# 28Pins_Schematic.net
KiCad netlist of a schematic drawn in Altium Designer
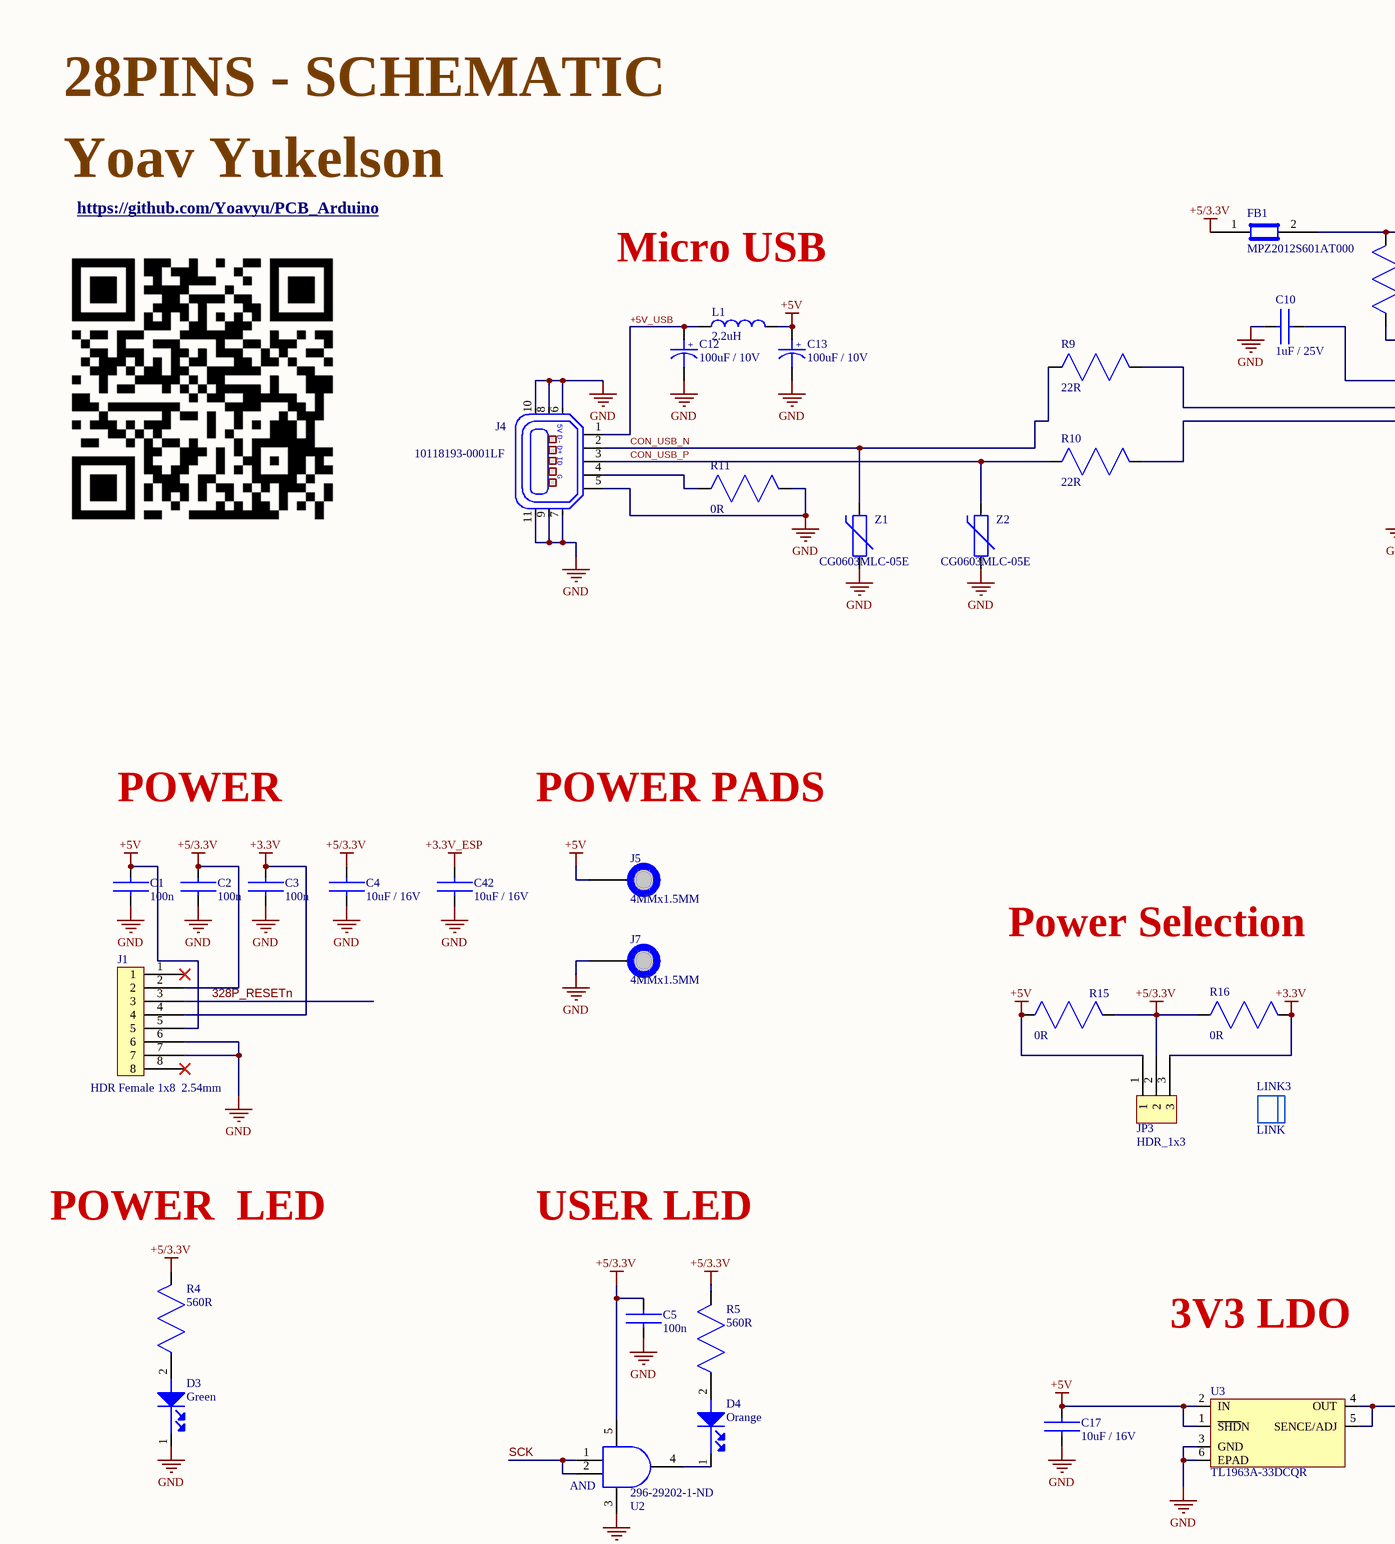
[diagram p0: 28Pins_Schematic.SchDoc, top left]
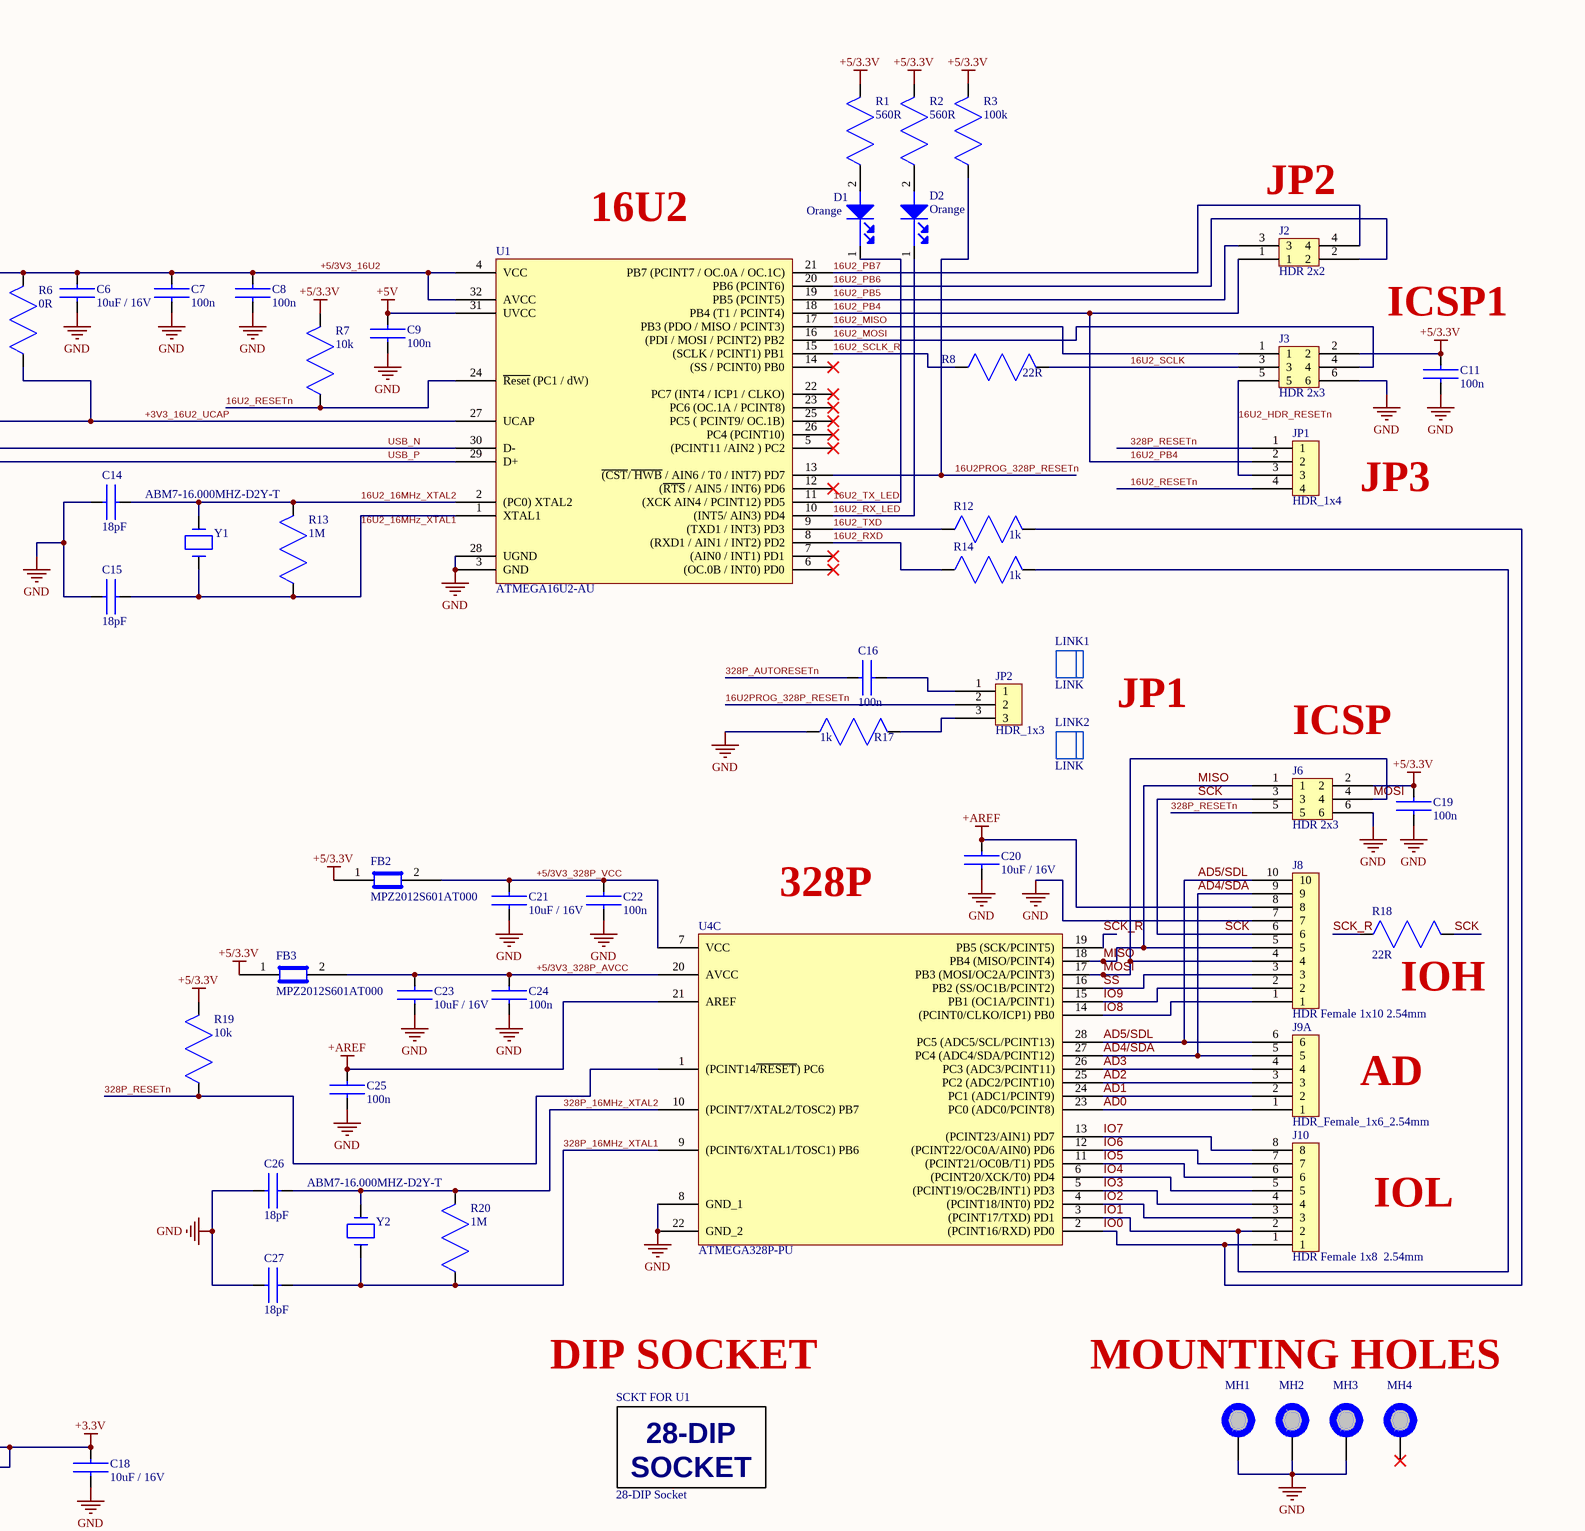
[diagram p1: 28Pins_Schematic.SchDoc, top right]
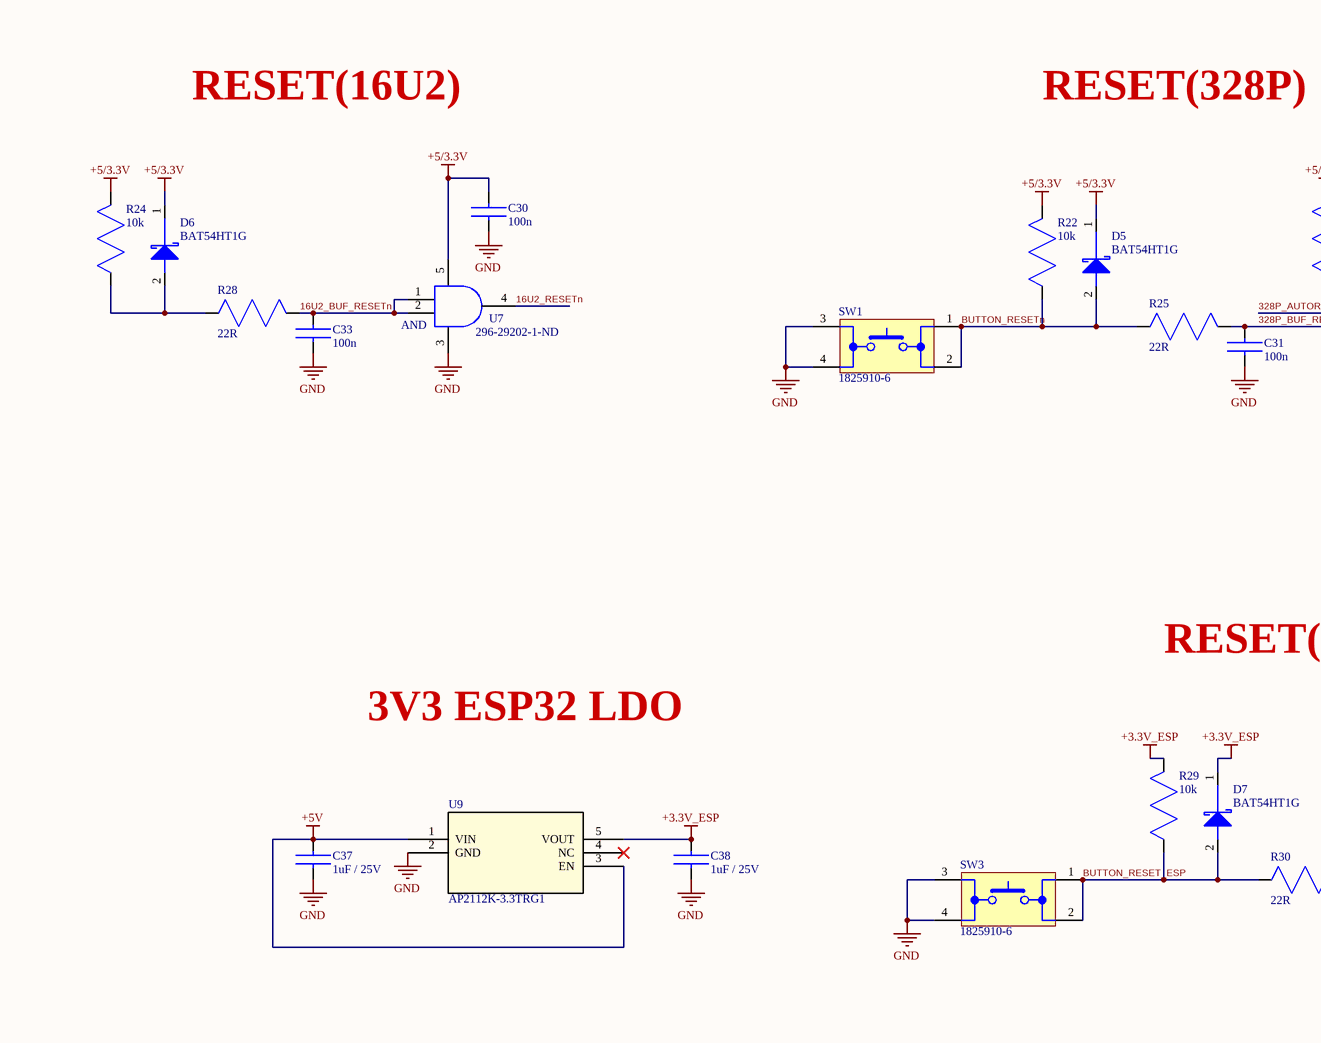
[diagram p2: 28Pins_Schematic.SchDoc, bottom left]
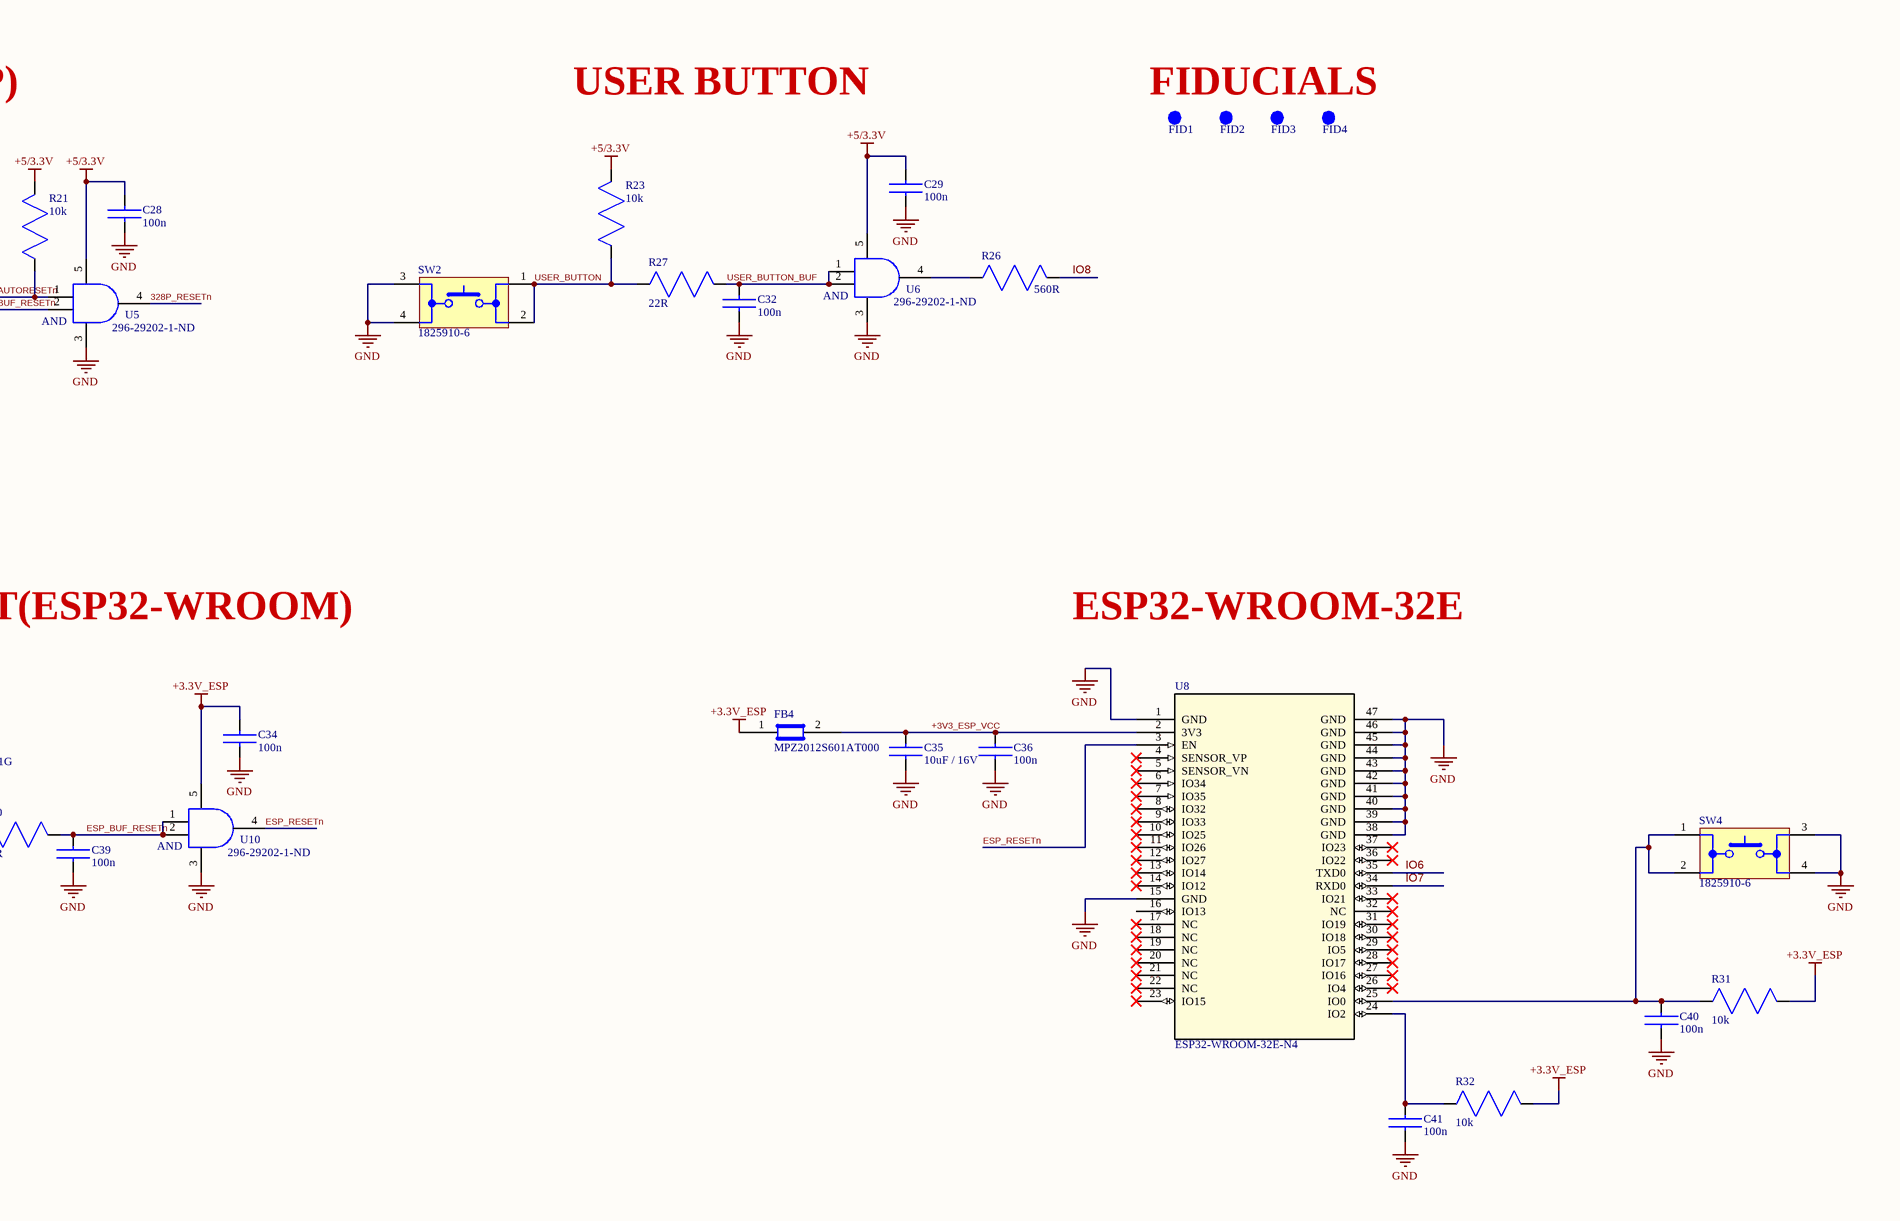
[diagram p3: 28Pins_Schematic.SchDoc, bottom right]

(export (version "E")
  (design (tool "Eeschema 10.0.6"))
  (components
    (comp (ref "C1")
      (value "100n")
      (footprint "C0805")
      (description "C Series 0805 0.1 uF 50 V ±10 % Tolerance X7R SMT Multilayer Ceramic Capacitor")
      (fields
        (field (name "MANUFACTURER") "TDK")
        (field (name "MANUFACTURER PART NUMBER") "C2012X7R1H104K085AA")
      )
      (libsource (lib "28Pins_Project_V1I1") (part "C2012X7R1H104K085AA"))
    )
    (comp (ref "C2")
      (value "100n")
      (footprint "C0805")
      (description "C Series 0805 0.1 uF 50 V ±10 % Tolerance X7R SMT Multilayer Ceramic Capacitor")
      (fields
        (field (name "MANUFACTURER") "TDK")
        (field (name "MANUFACTURER PART NUMBER") "C2012X7R1H104K085AA")
      )
      (libsource (lib "28Pins_Project_V1I1") (part "C2012X7R1H104K085AA"))
    )
    (comp (ref "C3")
      (value "100n")
      (footprint "C0805")
      (description "C Series 0805 0.1 uF 50 V ±10 % Tolerance X7R SMT Multilayer Ceramic Capacitor")
      (fields
        (field (name "MANUFACTURER") "TDK")
        (field (name "MANUFACTURER PART NUMBER") "C2012X7R1H104K085AA")
      )
      (libsource (lib "28Pins_Project_V1I1") (part "C2012X7R1H104K085AA"))
    )
    (comp (ref "C4")
      (value "10uF / 16V")
      (footprint "C0805")
      (description "C Series 0805 10 uF 16 V ±10 % Tolerance X5R SMT Multilayer Ceramic Capacitor")
      (fields
        (field (name "MANUFACTURER") "TDK")
        (field (name "MANUFACTURER PART NUMBER") "C2012X5R1C106K085AC")
      )
      (libsource (lib "28Pins_Project_V1I1") (part "C2012X5R1C106K085AC"))
    )
    (comp (ref "C5")
      (value "100n")
      (footprint "C0805")
      (description "C Series 0805 0.1 uF 50 V ±10 % Tolerance X7R SMT Multilayer Ceramic Capacitor")
      (fields
        (field (name "MANUFACTURER") "TDK")
        (field (name "MANUFACTURER PART NUMBER") "C2012X7R1H104K085AA")
      )
      (libsource (lib "28Pins_Project_V1I1") (part "C2012X7R1H104K085AA"))
    )
    (comp (ref "C6")
      (value "10uF / 16V")
      (footprint "C0805")
      (description "C Series 0805 10 uF 16 V ±10 % Tolerance X5R SMT Multilayer Ceramic Capacitor")
      (fields
        (field (name "MANUFACTURER") "TDK")
        (field (name "MANUFACTURER PART NUMBER") "C2012X5R1C106K085AC")
      )
      (libsource (lib "28Pins_Project_V1I1") (part "C2012X5R1C106K085AC"))
    )
    (comp (ref "C7")
      (value "100n")
      (footprint "C0805")
      (description "C Series 0805 0.1 uF 50 V ±10 % Tolerance X7R SMT Multilayer Ceramic Capacitor")
      (fields
        (field (name "MANUFACTURER") "TDK")
        (field (name "MANUFACTURER PART NUMBER") "C2012X7R1H104K085AA")
      )
      (libsource (lib "28Pins_Project_V1I1") (part "C2012X7R1H104K085AA"))
    )
    (comp (ref "C8")
      (value "100n")
      (footprint "C0805")
      (description "C Series 0805 0.1 uF 50 V ±10 % Tolerance X7R SMT Multilayer Ceramic Capacitor")
      (fields
        (field (name "MANUFACTURER") "TDK")
        (field (name "MANUFACTURER PART NUMBER") "C2012X7R1H104K085AA")
      )
      (libsource (lib "28Pins_Project_V1I1") (part "C2012X7R1H104K085AA"))
    )
    (comp (ref "C9")
      (value "100n")
      (footprint "C0805")
      (description "C Series 0805 0.1 uF 50 V ±10 % Tolerance X7R SMT Multilayer Ceramic Capacitor")
      (fields
        (field (name "MANUFACTURER") "TDK")
        (field (name "MANUFACTURER PART NUMBER") "C2012X7R1H104K085AA")
      )
      (libsource (lib "28Pins_Project_V1I1") (part "C2012X7R1H104K085AA"))
    )
    (comp (ref "C10")
      (value "1uF / 25V")
      (footprint "C0805")
      (description "C Series 0805 1 uF 25 V ±10% Tolerance X5R SMT Multilayer Ceramic Capacitor")
      (fields
        (field (name "MANUFACTURER") "TDK")
        (field (name "MANUFACTURER PART NUMBER") "C2012X5R1E105K125AA")
      )
      (libsource (lib "28Pins_Project_V1I1") (part "C2012X5R1E105K125AA"))
    )
    (comp (ref "C11")
      (value "100n")
      (footprint "C0805")
      (description "C Series 0805 0.1 uF 50 V ±10 % Tolerance X7R SMT Multilayer Ceramic Capacitor")
      (fields
        (field (name "MANUFACTURER") "TDK")
        (field (name "MANUFACTURER PART NUMBER") "C2012X7R1H104K085AA")
      )
      (libsource (lib "28Pins_Project_V1I1") (part "C2012X7R1H104K085AA"))
    )
    (comp (ref "C12")
      (value "100uF / 10V")
      (footprint "C_ALU_C_SIZE")
      (description "Radial Can - SMD ALUMINUM ELECTROLYTIC CAPACITOR S 10V 100muF ±20% 0.197Dia 5.00mm")
      (fields
        (field (name "MANUFACTURER") "Panasonic")
        (field (name "MANUFACTURER PART NUMBER") "EEE-1AA101WR")
      )
      (libsource (lib "28Pins_Project_V1I1") (part "EEE-1AA101WR"))
    )
    (comp (ref "C13")
      (value "100uF / 10V")
      (footprint "C_ALU_C_SIZE")
      (description "Radial Can - SMD ALUMINUM ELECTROLYTIC CAPACITOR S 10V 100muF ±20% 0.197Dia 5.00mm")
      (fields
        (field (name "MANUFACTURER") "Panasonic")
        (field (name "MANUFACTURER PART NUMBER") "EEE-1AA101WR")
      )
      (libsource (lib "28Pins_Project_V1I1") (part "EEE-1AA101WR"))
    )
    (comp (ref "C14")
      (value "18pF")
      (footprint "C0805")
      (description "SMD Comm C0G 0805 (2012Metric) Ceramic Capacitor 0.079Lx0.049W 2.00mmx1.25mm C0G NP0 ±5% 18pF")
      (fields
        (field (name "MANUFACTURER") "KEMET")
        (field (name "MANUFACTURER PART NUMBER") "C0805C180J5GACTU")
      )
      (libsource (lib "28Pins_Project_V1I1") (part "C0805C180J5GACTU"))
    )
    (comp (ref "C15")
      (value "18pF")
      (footprint "C0805")
      (description "SMD Comm C0G 0805 (2012Metric) Ceramic Capacitor 0.079Lx0.049W 2.00mmx1.25mm C0G NP0 ±5% 18pF")
      (fields
        (field (name "MANUFACTURER") "KEMET")
        (field (name "MANUFACTURER PART NUMBER") "C0805C180J5GACTU")
      )
      (libsource (lib "28Pins_Project_V1I1") (part "C0805C180J5GACTU"))
    )
    (comp (ref "C16")
      (value "100n")
      (footprint "C0805")
      (description "C Series 0805 0.1 uF 50 V ±10 % Tolerance X7R SMT Multilayer Ceramic Capacitor")
      (fields
        (field (name "MANUFACTURER") "TDK")
        (field (name "MANUFACTURER PART NUMBER") "C2012X7R1H104K085AA")
      )
      (libsource (lib "28Pins_Project_V1I1") (part "C2012X7R1H104K085AA"))
    )
    (comp (ref "C17")
      (value "10uF / 16V")
      (footprint "C0805")
      (description "C Series 0805 10 uF 16 V ±10 % Tolerance X5R SMT Multilayer Ceramic Capacitor")
      (fields
        (field (name "MANUFACTURER") "TDK")
        (field (name "MANUFACTURER PART NUMBER") "C2012X5R1C106K085AC")
      )
      (libsource (lib "28Pins_Project_V1I1") (part "C2012X5R1C106K085AC"))
    )
    (comp (ref "C18")
      (value "10uF / 16V")
      (footprint "C0805")
      (description "C Series 0805 10 uF 16 V ±10 % Tolerance X5R SMT Multilayer Ceramic Capacitor")
      (fields
        (field (name "MANUFACTURER") "TDK")
        (field (name "MANUFACTURER PART NUMBER") "C2012X5R1C106K085AC")
      )
      (libsource (lib "28Pins_Project_V1I1") (part "C2012X5R1C106K085AC"))
    )
    (comp (ref "C19")
      (value "100n")
      (footprint "C0805")
      (description "C Series 0805 0.1 uF 50 V ±10 % Tolerance X7R SMT Multilayer Ceramic Capacitor")
      (fields
        (field (name "MANUFACTURER") "TDK")
        (field (name "MANUFACTURER PART NUMBER") "C2012X7R1H104K085AA")
      )
      (libsource (lib "28Pins_Project_V1I1") (part "C2012X7R1H104K085AA"))
    )
    (comp (ref "C20")
      (value "10uF / 16V")
      (footprint "C0805")
      (description "C Series 0805 10 uF 16 V ±10 % Tolerance X5R SMT Multilayer Ceramic Capacitor")
      (fields
        (field (name "MANUFACTURER") "TDK")
        (field (name "MANUFACTURER PART NUMBER") "C2012X5R1C106K085AC")
      )
      (libsource (lib "28Pins_Project_V1I1") (part "C2012X5R1C106K085AC"))
    )
    (comp (ref "C21")
      (value "10uF / 16V")
      (footprint "C0805")
      (description "C Series 0805 10 uF 16 V ±10 % Tolerance X5R SMT Multilayer Ceramic Capacitor")
      (fields
        (field (name "MANUFACTURER") "TDK")
        (field (name "MANUFACTURER PART NUMBER") "C2012X5R1C106K085AC")
      )
      (libsource (lib "28Pins_Project_V1I1") (part "C2012X5R1C106K085AC"))
    )
    (comp (ref "C22")
      (value "100n")
      (footprint "C0805")
      (description "C Series 0805 0.1 uF 50 V ±10 % Tolerance X7R SMT Multilayer Ceramic Capacitor")
      (fields
        (field (name "MANUFACTURER") "TDK")
        (field (name "MANUFACTURER PART NUMBER") "C2012X7R1H104K085AA")
      )
      (libsource (lib "28Pins_Project_V1I1") (part "C2012X7R1H104K085AA"))
    )
    (comp (ref "C23")
      (value "10uF / 16V")
      (footprint "C0805")
      (description "C Series 0805 10 uF 16 V ±10 % Tolerance X5R SMT Multilayer Ceramic Capacitor")
      (fields
        (field (name "MANUFACTURER") "TDK")
        (field (name "MANUFACTURER PART NUMBER") "C2012X5R1C106K085AC")
      )
      (libsource (lib "28Pins_Project_V1I1") (part "C2012X5R1C106K085AC"))
    )
    (comp (ref "C24")
      (value "100n")
      (footprint "C0805")
      (description "C Series 0805 0.1 uF 50 V ±10 % Tolerance X7R SMT Multilayer Ceramic Capacitor")
      (fields
        (field (name "MANUFACTURER") "TDK")
        (field (name "MANUFACTURER PART NUMBER") "C2012X7R1H104K085AA")
      )
      (libsource (lib "28Pins_Project_V1I1") (part "C2012X7R1H104K085AA"))
    )
    (comp (ref "C25")
      (value "100n")
      (footprint "C0805")
      (description "C Series 0805 0.1 uF 50 V ±10 % Tolerance X7R SMT Multilayer Ceramic Capacitor")
      (fields
        (field (name "MANUFACTURER") "TDK")
        (field (name "MANUFACTURER PART NUMBER") "C2012X7R1H104K085AA")
      )
      (libsource (lib "28Pins_Project_V1I1") (part "C2012X7R1H104K085AA"))
    )
    (comp (ref "C26")
      (value "18pF")
      (footprint "C0805")
      (description "SMD Comm C0G 0805 (2012Metric) Ceramic Capacitor 0.079Lx0.049W 2.00mmx1.25mm C0G NP0 ±5% 18pF")
      (fields
        (field (name "MANUFACTURER") "KEMET")
        (field (name "MANUFACTURER PART NUMBER") "C0805C180J5GACTU")
      )
      (libsource (lib "28Pins_Project_V1I1") (part "C0805C180J5GACTU"))
    )
    (comp (ref "C27")
      (value "18pF")
      (footprint "C0805")
      (description "SMD Comm C0G 0805 (2012Metric) Ceramic Capacitor 0.079Lx0.049W 2.00mmx1.25mm C0G NP0 ±5% 18pF")
      (fields
        (field (name "MANUFACTURER") "KEMET")
        (field (name "MANUFACTURER PART NUMBER") "C0805C180J5GACTU")
      )
      (libsource (lib "28Pins_Project_V1I1") (part "C0805C180J5GACTU"))
    )
    (comp (ref "C28")
      (value "100n")
      (footprint "C0805")
      (description "C Series 0805 0.1 uF 50 V ±10 % Tolerance X7R SMT Multilayer Ceramic Capacitor")
      (fields
        (field (name "MANUFACTURER") "TDK")
        (field (name "MANUFACTURER PART NUMBER") "C2012X7R1H104K085AA")
      )
      (libsource (lib "28Pins_Project_V1I1") (part "C2012X7R1H104K085AA"))
    )
    (comp (ref "C29")
      (value "100n")
      (footprint "C0805")
      (description "C Series 0805 0.1 uF 50 V ±10 % Tolerance X7R SMT Multilayer Ceramic Capacitor")
      (fields
        (field (name "MANUFACTURER") "TDK")
        (field (name "MANUFACTURER PART NUMBER") "C2012X7R1H104K085AA")
      )
      (libsource (lib "28Pins_Project_V1I1") (part "C2012X7R1H104K085AA"))
    )
    (comp (ref "C30")
      (value "100n")
      (footprint "C0805")
      (description "C Series 0805 0.1 uF 50 V ±10 % Tolerance X7R SMT Multilayer Ceramic Capacitor")
      (fields
        (field (name "MANUFACTURER") "TDK")
        (field (name "MANUFACTURER PART NUMBER") "C2012X7R1H104K085AA")
      )
      (libsource (lib "28Pins_Project_V1I1") (part "C2012X7R1H104K085AA"))
    )
    (comp (ref "C31")
      (value "100n")
      (footprint "C0805")
      (description "C Series 0805 0.1 uF 50 V ±10 % Tolerance X7R SMT Multilayer Ceramic Capacitor")
      (fields
        (field (name "MANUFACTURER") "TDK")
        (field (name "MANUFACTURER PART NUMBER") "C2012X7R1H104K085AA")
      )
      (libsource (lib "28Pins_Project_V1I1") (part "C2012X7R1H104K085AA"))
    )
    (comp (ref "C32")
      (value "100n")
      (footprint "C0805")
      (description "C Series 0805 0.1 uF 50 V ±10 % Tolerance X7R SMT Multilayer Ceramic Capacitor")
      (fields
        (field (name "MANUFACTURER") "TDK")
        (field (name "MANUFACTURER PART NUMBER") "C2012X7R1H104K085AA")
      )
      (libsource (lib "28Pins_Project_V1I1") (part "C2012X7R1H104K085AA"))
    )
    (comp (ref "C33")
      (value "100n")
      (footprint "C0805")
      (description "C Series 0805 0.1 uF 50 V ±10 % Tolerance X7R SMT Multilayer Ceramic Capacitor")
      (fields
        (field (name "MANUFACTURER") "TDK")
        (field (name "MANUFACTURER PART NUMBER") "C2012X7R1H104K085AA")
      )
      (libsource (lib "28Pins_Project_V1I1") (part "C2012X7R1H104K085AA"))
    )
    (comp (ref "C34")
      (value "100n")
      (footprint "C0805")
      (description "C Series 0805 0.1 uF 50 V ±10 % Tolerance X7R SMT Multilayer Ceramic Capacitor")
      (fields
        (field (name "MANUFACTURER") "TDK")
        (field (name "MANUFACTURER PART NUMBER") "C2012X7R1H104K085AA")
      )
      (libsource (lib "28Pins_Project_V1I1") (part "C2012X7R1H104K085AA"))
    )
    (comp (ref "C35")
      (value "10uF / 16V")
      (footprint "C0805")
      (description "C Series 0805 10 uF 16 V ±10 % Tolerance X5R SMT Multilayer Ceramic Capacitor")
      (fields
        (field (name "MANUFACTURER") "TDK")
        (field (name "MANUFACTURER PART NUMBER") "C2012X5R1C106K085AC")
      )
      (libsource (lib "28Pins_Project_V1I1") (part "C2012X5R1C106K085AC"))
    )
    (comp (ref "C36")
      (value "100n")
      (footprint "C0805")
      (description "C Series 0805 0.1 uF 50 V ±10 % Tolerance X7R SMT Multilayer Ceramic Capacitor")
      (fields
        (field (name "MANUFACTURER") "TDK")
        (field (name "MANUFACTURER PART NUMBER") "C2012X7R1H104K085AA")
      )
      (libsource (lib "28Pins_Project_V1I1") (part "C2012X7R1H104K085AA"))
    )
    (comp (ref "C37")
      (value "1uF / 25V")
      (footprint "C0805")
      (description "C Series 0805 1 uF 25 V ±10% Tolerance X5R SMT Multilayer Ceramic Capacitor")
      (fields
        (field (name "MANUFACTURER") "TDK")
        (field (name "MANUFACTURER PART NUMBER") "C2012X5R1E105K125AA")
      )
      (libsource (lib "28Pins_Project_V1I1") (part "C2012X5R1E105K125AA"))
    )
    (comp (ref "C38")
      (value "1uF / 25V")
      (footprint "C0805")
      (description "C Series 0805 1 uF 25 V ±10% Tolerance X5R SMT Multilayer Ceramic Capacitor")
      (fields
        (field (name "MANUFACTURER") "TDK")
        (field (name "MANUFACTURER PART NUMBER") "C2012X5R1E105K125AA")
      )
      (libsource (lib "28Pins_Project_V1I1") (part "C2012X5R1E105K125AA"))
    )
    (comp (ref "C39")
      (value "100n")
      (footprint "C0805")
      (description "C Series 0805 0.1 uF 50 V ±10 % Tolerance X7R SMT Multilayer Ceramic Capacitor")
      (fields
        (field (name "MANUFACTURER") "TDK")
        (field (name "MANUFACTURER PART NUMBER") "C2012X7R1H104K085AA")
      )
      (libsource (lib "28Pins_Project_V1I1") (part "C2012X7R1H104K085AA"))
    )
    (comp (ref "C40")
      (value "100n")
      (footprint "C0805")
      (description "C Series 0805 0.1 uF 50 V ±10 % Tolerance X7R SMT Multilayer Ceramic Capacitor")
      (fields
        (field (name "MANUFACTURER") "TDK")
        (field (name "MANUFACTURER PART NUMBER") "C2012X7R1H104K085AA")
      )
      (libsource (lib "28Pins_Project_V1I1") (part "C2012X7R1H104K085AA"))
    )
    (comp (ref "C41")
      (value "100n")
      (footprint "C0805")
      (description "C Series 0805 0.1 uF 50 V ±10 % Tolerance X7R SMT Multilayer Ceramic Capacitor")
      (fields
        (field (name "MANUFACTURER") "TDK")
        (field (name "MANUFACTURER PART NUMBER") "C2012X7R1H104K085AA")
      )
      (libsource (lib "28Pins_Project_V1I1") (part "C2012X7R1H104K085AA"))
    )
    (comp (ref "C42")
      (value "10uF / 16V")
      (footprint "C0805")
      (description "C Series 0805 10 uF 16 V ±10 % Tolerance X5R SMT Multilayer Ceramic Capacitor")
      (fields
        (field (name "MANUFACTURER") "TDK")
        (field (name "MANUFACTURER PART NUMBER") "C2012X5R1C106K085AC")
      )
      (libsource (lib "28Pins_Project_V1I1") (part "C2012X5R1C106K085AC"))
    )
    (comp (ref "D1")
      (value "Orange")
      (footprint "LED_0603")
      (description "LED Uni-Color Orange 610nm Automotive 2-Pin Chip 0603(1608Metric) T/R")
      (fields
        (field (name "MANUFACTURER") "Osram")
        (field (name "MANUFACTURER PART NUMBER") "LO L29K-H2K1-24-0-2-R18-Z")
      )
      (libsource (lib "28Pins_Project_V1I1") (part "LO L29K-H2K1-24-0-2-R18-Z"))
    )
    (comp (ref "D2")
      (value "Orange")
      (footprint "LED_0603")
      (description "LED Uni-Color Orange 610nm Automotive 2-Pin Chip 0603(1608Metric) T/R")
      (fields
        (field (name "MANUFACTURER") "Osram")
        (field (name "MANUFACTURER PART NUMBER") "LO L29K-H2K1-24-0-2-R18-Z")
      )
      (libsource (lib "28Pins_Project_V1I1") (part "LO L29K-H2K1-24-0-2-R18-Z"))
    )
    (comp (ref "D3")
      (value "Green")
      (footprint "LED_0603")
      (description "LED Uni-Color Green 572nm 2-Pin Chip 0603(1608Metric) T/R")
      (fields
        (field (name "MANUFACTURER") "Osram")
        (field (name "MANUFACTURER PART NUMBER") "LG L29K-G2J1-24-0-2-R18-Z")
      )
      (libsource (lib "28Pins_Project_V1I1") (part "LG L29K-G2J1-24-0-2-R18-Z"))
    )
    (comp (ref "D4")
      (value "Orange")
      (footprint "LED_0603")
      (description "LED Uni-Color Orange 610nm Automotive 2-Pin Chip 0603(1608Metric) T/R")
      (fields
        (field (name "MANUFACTURER") "Osram")
        (field (name "MANUFACTURER PART NUMBER") "LO L29K-H2K1-24-0-2-R18-Z")
      )
      (libsource (lib "28Pins_Project_V1I1") (part "LO L29K-H2K1-24-0-2-R18-Z"))
    )
    (comp (ref "D5")
      (value "BAT54HT1G")
      (footprint "SOD323")
      (description "Small Signal Schottky Diode, Single, 30 V, 200 Ma, 800 Mv, 600 Ma, 150 C")
      (fields (field (name "MANUFACTURER") "onsemi"))
      (libsource (lib "28Pins_Project_V1I1") (part "BAT54HT1G"))
    )
    (comp (ref "D6")
      (value "BAT54HT1G")
      (footprint "SOD323")
      (description "Small Signal Schottky Diode, Single, 30 V, 200 Ma, 800 Mv, 600 Ma, 150 C")
      (fields (field (name "MANUFACTURER") "onsemi"))
      (libsource (lib "28Pins_Project_V1I1") (part "BAT54HT1G"))
    )
    (comp (ref "D7")
      (value "BAT54HT1G")
      (footprint "SOD323")
      (description "Small Signal Schottky Diode, Single, 30 V, 200 Ma, 800 Mv, 600 Ma, 150 C")
      (fields (field (name "MANUFACTURER") "onsemi"))
      (libsource (lib "28Pins_Project_V1I1") (part "BAT54HT1G"))
    )
    (comp (ref "FB1")
      (value "MPZ2012S601AT000")
      (footprint "C0805")
      (description "Ferrite Beads Multi-Layer Power 600Ohm 25% 100MHz 2A 100mOhm DCR 0805 T/R")
      (fields (field (name "MANUFACTURER") "TDK") (field (name "TOLERANCE") "25%"))
      (libsource (lib "28Pins_Project_V1I1") (part "MPZ2012S601AT000"))
    )
    (comp (ref "FB2")
      (value "MPZ2012S601AT000")
      (footprint "C0805")
      (description "Ferrite Beads Multi-Layer Power 600Ohm 25% 100MHz 2A 100mOhm DCR 0805 T/R")
      (fields (field (name "MANUFACTURER") "TDK") (field (name "TOLERANCE") "25%"))
      (libsource (lib "28Pins_Project_V1I1") (part "MPZ2012S601AT000"))
    )
    (comp (ref "FB3")
      (value "MPZ2012S601AT000")
      (footprint "C0805")
      (description "Ferrite Beads Multi-Layer Power 600Ohm 25% 100MHz 2A 100mOhm DCR 0805 T/R")
      (fields (field (name "MANUFACTURER") "TDK") (field (name "TOLERANCE") "25%"))
      (libsource (lib "28Pins_Project_V1I1") (part "MPZ2012S601AT000"))
    )
    (comp (ref "FB4")
      (value "MPZ2012S601AT000")
      (footprint "C0805")
      (description "Ferrite Beads Multi-Layer Power 600Ohm 25% 100MHz 2A 100mOhm DCR 0805 T/R")
      (fields (field (name "MANUFACTURER") "TDK") (field (name "TOLERANCE") "25%"))
      (libsource (lib "28Pins_Project_V1I1") (part "MPZ2012S601AT000"))
    )
    (comp (ref "FID1")
      (value "FID_1MMC")
      (footprint "FID_40X120D")
      (libsource (lib "28Pins_Project_V1I1") (part "FID_1MMC"))
    )
    (comp (ref "FID2")
      (value "FID_1MMC")
      (footprint "FID_40X120D")
      (libsource (lib "28Pins_Project_V1I1") (part "FID_1MMC"))
    )
    (comp (ref "FID3")
      (value "FID_1MMC")
      (footprint "FID_40X120D")
      (libsource (lib "28Pins_Project_V1I1") (part "FID_1MMC"))
    )
    (comp (ref "FID4")
      (value "FID_1MMC")
      (footprint "FID_40X120D")
      (libsource (lib "28Pins_Project_V1I1") (part "FID_1MMC"))
    )
    (comp (ref "J1")
      (value "HDR Female 1x8  2.54mm")
      (footprint "Hdr_Female_1x8_2.54mm")
      (description "2.54mm (0.1) Pitch SIL Vertical PC Tail Socket Assembly, selective gold + tin, 8 contacts\"")
      (fields (field (name "MANUFACTURER") "Harwin") (field (name "MANUFACTURER PART NUMBER") "M20-7820842"))
      (libsource (lib "") (part "M20-7820842_1"))
    )
    (comp (ref "J2")
      (value "HDR 2x2")
      (footprint "HDR_2x2_2.54mm")
      (description "2.54mm Pitch C-Grid Breakaway Header Dual Row Vertical High Temperature 4 Circuits 0.38")
      (fields (field (name "MANUFACTURER") "Molex") (field (name "MANUFACTURER PART NUMBER") "10-89-7042"))
      (libsource (lib "28Pins_Project_V1I1") (part "10-89-7042"))
    )
    (comp (ref "J3")
      (value "HDR 2x3")
      (footprint "HDR_2x3_2.54mm")
      (description "Conn; Rect; Header; Unshrouded; 6 Pos; 2.54mm Pitch; 2-Row; Thru-Hole; BergStik")
      (fields
        (field (name "MANUFACTURER") "Amphenol Communications Solutions")
        (field (name "MANUFACTURER PART NUMBER") "67997-106HLF")
      )
      (libsource (lib "28Pins_Project_V1I1") (part "67997-106HLF"))
    )
    (comp (ref "J4")
      (value "10118193-0001LF")
      (footprint "10118193")
      (description "USB - micro B USB 2.0 Receptacle Connector 5 Position Surface Mount, Right Angle, Horizontal")
      (fields (field (name "MANUFACTURER") "Amphenol Communications Solutions"))
      (libsource (lib "28Pins_Project_V1I1") (part "10118193-0001LF"))
    )
    (comp (ref "J5")
      (value "4MMx1.5MM")
      (footprint "PAD_WITH_HOLE_4MMx1.5mm")
      (description "Pad with a hole 4MMx1.5MM")
      (libsource (lib "28Pins_Project_V1I1") (part "PAD_WITH_HOLE_4MMx1.5MM"))
    )
    (comp (ref "J6")
      (value "HDR 2x3")
      (footprint "HDR_2x3_2.54mm")
      (description "Conn; Rect; Header; Unshrouded; 6 Pos; 2.54mm Pitch; 2-Row; Thru-Hole; BergStik")
      (fields
        (field (name "MANUFACTURER") "Amphenol Communications Solutions")
        (field (name "MANUFACTURER PART NUMBER") "67997-106HLF")
      )
      (libsource (lib "28Pins_Project_V1I1") (part "67997-106HLF"))
    )
    (comp (ref "J7")
      (value "4MMx1.5MM")
      (footprint "PAD_WITH_HOLE_4MMx1.5mm")
      (description "Pad with a hole 4MMx1.5MM")
      (libsource (lib "28Pins_Project_V1I1") (part "PAD_WITH_HOLE_4MMx1.5MM"))
    )
    (comp (ref "J8")
      (value "HDR Female 1x10 2.54mm")
      (footprint "Hdr_Female_1x10_2.54mm")
      (description "Conn Socket Strip Receptacle 10 Position 2.54mm Solder Straight Through Hole Tube")
      (fields (field (name "MANUFACTURER") "Harwin") (field (name "MANUFACTURER PART NUMBER") "M20-7821046"))
      (libsource (lib "28Pins_Project_V1I1") (part "M20-7821046"))
    )
    (comp (ref "J9")
      (value "HDR_Female_1x6_2.54mm")
      (footprint "Hdr_Female_1x6_2.54mm")
      (description "Conn Socket Strip Receptacle 6 Position 2.54mm Solder Straight Through Hole Tube")
      (fields (field (name "MANUFACTURER") "Harwin") (field (name "MANUFACTURER PART NUMBER") "M20-7820646"))
      (libsource (lib "28Pins_Project_V1I1") (part "M20-7820646"))
    )
    (comp (ref "J10")
      (value "HDR Female 1x8  2.54mm")
      (footprint "Hdr_Female_1x8_2.54mm")
      (description "2.54mm (0.1) Pitch SIL Vertical PC Tail Socket Assembly, selective gold + tin, 8 contacts\"")
      (fields (field (name "MANUFACTURER") "Harwin") (field (name "MANUFACTURER PART NUMBER") "M20-7820842"))
      (libsource (lib "28Pins_Project_V1I1") (part "M20-7820842"))
    )
    (comp (ref "JP1")
      (value "HDR_1x4")
      (footprint "Hdr_1x4_2.54mm")
      (description "Conn Unshrouded Header HDR 4 POS 2.54mm Solder ST Top Entry Thru-Hole BergStik® Bulk")
      (fields
        (field (name "MANUFACTURER") "Amphenol Communications Solutions")
        (field (name "MANUFACTURER PART NUMBER") "68001-204HLF")
      )
      (libsource (lib "28Pins_Project_V1I1") (part "68001-204HLF"))
    )
    (comp (ref "JP2")
      (value "HDR_1x3")
      (footprint "Hdr_Female_1x3_2.54mm")
      (description "Conn Unshrouded Header HDR 3 POS 2.54mm Solder ST Top Entry Thru-Hole BergStik® Bulk")
      (fields
        (field (name "MANUFACTURER") "Amphenol Communications Solutions")
        (field (name "MANUFACTURER PART NUMBER") "68000-103HLF")
      )
      (libsource (lib "") (part "68000-103HLF_1"))
    )
    (comp (ref "JP3")
      (value "HDR_1x3")
      (footprint "Hdr_Female_1x3_2.54mm")
      (description "Conn Unshrouded Header HDR 3 POS 2.54mm Solder ST Top Entry Thru-Hole BergStik® Bulk")
      (fields
        (field (name "MANUFACTURER") "Amphenol Communications Solutions")
        (field (name "MANUFACTURER PART NUMBER") "68000-103HLF")
      )
      (libsource (lib "28Pins_Project_V1I1") (part "68000-103HLF"))
    )
    (comp (ref "L1")
      (value "2.2uH")
      (footprint "C1210_IND")
      (description "Inductor Chip Molded Wirewound 2.2uH 20% 0805 T/R")
      (fields
        (field (name "MANUFACTURER") "KEMET")
        (field (name "MANUFACTURER PART NUMBER") "L0805B2R2MDWLT")
      )
      (libsource (lib "28Pins_Project_V1I1") (part "L0805B2R2MDWLT"))
    )
    (comp (ref "LINK1")
      (value "LINK")
      (description "2 Position 2.54 mm Centerline Single Circuit Open Top Jumper")
      (fields
        (field (name "MANUFACTURER") "Sullins")
        (field (name "MANUFACTURER PART NUMBER") "QPC02SXGN-RC")
      )
      (libsource (lib "28Pins_Project_V1I1") (part "QPC02SXGN-RC"))
    )
    (comp (ref "LINK2")
      (value "LINK")
      (description "2 Position 2.54 mm Centerline Single Circuit Open Top Jumper")
      (fields
        (field (name "MANUFACTURER") "Sullins")
        (field (name "MANUFACTURER PART NUMBER") "QPC02SXGN-RC")
      )
      (libsource (lib "28Pins_Project_V1I1") (part "QPC02SXGN-RC"))
    )
    (comp (ref "LINK3")
      (value "LINK")
      (description "2 Position 2.54 mm Centerline Single Circuit Open Top Jumper")
      (fields
        (field (name "MANUFACTURER") "Sullins")
        (field (name "MANUFACTURER PART NUMBER") "QPC02SXGN-RC")
      )
      (libsource (lib "28Pins_Project_V1I1") (part "QPC02SXGN-RC"))
    )
    (comp (ref "MH1")
      (value "MH_7.4MMC_3.2MMD")
      (footprint "MH_7.4MMC_3.2MMD")
      (libsource (lib "28Pins_Project_V1I1") (part "MH_7.4MMC_3.2MMD"))
    )
    (comp (ref "MH2")
      (value "MH_7.4MMC_3.2MMD")
      (footprint "MH_7.4MMC_3.2MMD")
      (libsource (lib "28Pins_Project_V1I1") (part "MH_7.4MMC_3.2MMD"))
    )
    (comp (ref "MH3")
      (value "MH_7.4MMC_3.2MMD")
      (footprint "MH_7.4MMC_3.2MMD")
      (libsource (lib "28Pins_Project_V1I1") (part "MH_7.4MMC_3.2MMD"))
    )
    (comp (ref "MH4")
      (value "MH_7.4MMNC_3.2MMD")
      (footprint "MH_7.4MMNC_3.2MMD_NON_COPPER_NPTH")
      (libsource (lib "28Pins_Project_V1I1") (part "MH_7.4MMNC_3.2MMD"))
    )
    (comp (ref "R1")
      (value "560R")
      (footprint "R0805")
      (description "Res Thick Film 0805 560 Ohm 1% 0.125W(1/8W) ±100ppm/C Pad SMD T/R")
      (fields
        (field (name "MANUFACTURER") "Yageo Group")
        (field (name "MANUFACTURER PART NUMBER") "RC0805FR-07560RL")
      )
      (libsource (lib "28Pins_Project_V1I1") (part "RC0805FR-07560RL"))
    )
    (comp (ref "R2")
      (value "560R")
      (footprint "R0805")
      (description "Res Thick Film 0805 560 Ohm 1% 0.125W(1/8W) ±100ppm/C Pad SMD T/R")
      (fields
        (field (name "MANUFACTURER") "Yageo Group")
        (field (name "MANUFACTURER PART NUMBER") "RC0805FR-07560RL")
      )
      (libsource (lib "28Pins_Project_V1I1") (part "RC0805FR-07560RL"))
    )
    (comp (ref "R3")
      (value "100k")
      (footprint "R0805")
      (description "125mW Thick Film Resistors 150V ±100ppm/℃ ±1% 100kΩ 0805 Chip Resistor - Surface Mount ROHS")
      (fields
        (field (name "MANUFACTURER") "Yageo Group")
        (field (name "MANUFACTURER PART NUMBER") "RC0805FR-07100KL")
      )
      (libsource (lib "28Pins_Project_V1I1") (part "RC0805FR-07100KL"))
    )
    (comp (ref "R4")
      (value "560R")
      (footprint "R0805")
      (description "Res Thick Film 0805 560 Ohm 1% 0.125W(1/8W) ±100ppm/C Pad SMD T/R")
      (fields
        (field (name "MANUFACTURER") "Yageo Group")
        (field (name "MANUFACTURER PART NUMBER") "RC0805FR-07560RL")
      )
      (libsource (lib "28Pins_Project_V1I1") (part "RC0805FR-07560RL"))
    )
    (comp (ref "R5")
      (value "560R")
      (footprint "R0805")
      (description "Res Thick Film 0805 560 Ohm 1% 0.125W(1/8W) ±100ppm/C Pad SMD T/R")
      (fields
        (field (name "MANUFACTURER") "Yageo Group")
        (field (name "MANUFACTURER PART NUMBER") "RC0805FR-07560RL")
      )
      (libsource (lib "28Pins_Project_V1I1") (part "RC0805FR-07560RL"))
    )
    (comp (ref "R6")
      (value "0R")
      (footprint "R0805")
      (description "GENERAL PURPOSE CHIP RESISTOR Metal Glaze/thick Film, 0.125W, 0ohm, Surface Mount, 0805")
      (fields
        (field (name "MANUFACTURER") "Yageo Group")
        (field (name "MANUFACTURER PART NUMBER") "RC0805JR-070RL")
      )
      (libsource (lib "28Pins_Project_V1I1") (part "RC0805JR-070RL"))
    )
    (comp (ref "R7")
      (value "10k")
      (footprint "R0805")
      (description "Res Thick Film 0805 10K Ohm 1% 0.125W(1/8W) +/-100ppm/C Epoxy Pad SMD T/R")
      (fields
        (field (name "MANUFACTURER") "Yageo Group")
        (field (name "MANUFACTURER PART NUMBER") "RC0805FR-0710KL")
      )
      (libsource (lib "28Pins_Project_V1I1") (part "RC0805FR-0710KL"))
    )
    (comp (ref "R8")
      (value "22R")
      (footprint "R0805")
      (description "125mW Thick Film Resistors 150V ±1% ±200ppm/℃ 2.2Ω 0805 Chip Resistor - Surface Mount ROHS")
      (fields
        (field (name "MANUFACTURER") "Yageo Group")
        (field (name "MANUFACTURER PART NUMBER") "RC0805FR-072R2L")
      )
      (libsource (lib "28Pins_Project_V1I1") (part "RC0805FR-072R2L"))
    )
    (comp (ref "R9")
      (value "22R")
      (footprint "R0805")
      (description "125mW Thick Film Resistors 150V ±1% ±200ppm/℃ 2.2Ω 0805 Chip Resistor - Surface Mount ROHS")
      (fields
        (field (name "MANUFACTURER") "Yageo Group")
        (field (name "MANUFACTURER PART NUMBER") "RC0805FR-072R2L")
      )
      (libsource (lib "28Pins_Project_V1I1") (part "RC0805FR-072R2L"))
    )
    (comp (ref "R10")
      (value "22R")
      (footprint "R0805")
      (description "125mW Thick Film Resistors 150V ±1% ±200ppm/℃ 2.2Ω 0805 Chip Resistor - Surface Mount ROHS")
      (fields
        (field (name "MANUFACTURER") "Yageo Group")
        (field (name "MANUFACTURER PART NUMBER") "RC0805FR-072R2L")
      )
      (libsource (lib "28Pins_Project_V1I1") (part "RC0805FR-072R2L"))
    )
    (comp (ref "R11")
      (value "0R")
      (footprint "R0805")
      (description "GENERAL PURPOSE CHIP RESISTOR Metal Glaze/thick Film, 0.125W, 0ohm, Surface Mount, 0805")
      (fields
        (field (name "MANUFACTURER") "Yageo Group")
        (field (name "MANUFACTURER PART NUMBER") "RC0805JR-070RL")
      )
      (libsource (lib "28Pins_Project_V1I1") (part "RC0805JR-070RL"))
    )
    (comp (ref "R12")
      (value "1k")
      (footprint "R0805")
      (description "Resistor, thick film, SMD 0805 (2012), 1 kΩ, 0.125 W, ±1 %, RC0805FR-071KL")
      (fields
        (field (name "MANUFACTURER") "Yageo Group")
        (field (name "MANUFACTURER PART NUMBER") "RC0805FR-071KL")
      )
      (libsource (lib "28Pins_Project_V1I1") (part "RC0805FR-071KL"))
    )
    (comp (ref "R13")
      (value "1M")
      (footprint "R0805")
      (description "125mW Thick Film Resistors 150V ±100ppm/℃ ±1% 1MΩ 0805 Chip Resistor - Surface Mount ROHS")
      (fields
        (field (name "MANUFACTURER") "Yageo Group")
        (field (name "MANUFACTURER PART NUMBER") "RC0805FR-071ML")
      )
      (libsource (lib "28Pins_Project_V1I1") (part "RC0805FR-071ML"))
    )
    (comp (ref "R14")
      (value "1k")
      (footprint "R0805")
      (description "Resistor, thick film, SMD 0805 (2012), 1 kΩ, 0.125 W, ±1 %, RC0805FR-071KL")
      (fields
        (field (name "MANUFACTURER") "Yageo Group")
        (field (name "MANUFACTURER PART NUMBER") "RC0805FR-071KL")
      )
      (libsource (lib "28Pins_Project_V1I1") (part "RC0805FR-071KL"))
    )
    (comp (ref "R15")
      (value "0R")
      (footprint "R0805")
      (description "GENERAL PURPOSE CHIP RESISTOR Metal Glaze/thick Film, 0.125W, 0ohm, Surface Mount, 0805")
      (fields
        (field (name "MANUFACTURER") "Yageo Group")
        (field (name "MANUFACTURER PART NUMBER") "RC0805JR-070RL")
      )
      (libsource (lib "28Pins_Project_V1I1") (part "RC0805JR-070RL"))
    )
    (comp (ref "R16")
      (value "0R")
      (footprint "R0805")
      (description "GENERAL PURPOSE CHIP RESISTOR Metal Glaze/thick Film, 0.125W, 0ohm, Surface Mount, 0805")
      (fields
        (field (name "MANUFACTURER") "Yageo Group")
        (field (name "MANUFACTURER PART NUMBER") "RC0805JR-070RL")
      )
      (libsource (lib "28Pins_Project_V1I1") (part "RC0805JR-070RL"))
    )
    (comp (ref "R17")
      (value "1k")
      (footprint "R0805")
      (description "Resistor, thick film, SMD 0805 (2012), 1 kΩ, 0.125 W, ±1 %, RC0805FR-071KL")
      (fields
        (field (name "MANUFACTURER") "Yageo Group")
        (field (name "MANUFACTURER PART NUMBER") "RC0805FR-071KL")
      )
      (libsource (lib "28Pins_Project_V1I1") (part "RC0805FR-071KL"))
    )
    (comp (ref "R18")
      (value "22R")
      (footprint "R0805")
      (description "125mW Thick Film Resistors 150V ±1% ±200ppm/℃ 2.2Ω 0805 Chip Resistor - Surface Mount ROHS")
      (fields
        (field (name "MANUFACTURER") "Yageo Group")
        (field (name "MANUFACTURER PART NUMBER") "RC0805FR-072R2L")
      )
      (libsource (lib "28Pins_Project_V1I1") (part "RC0805FR-072R2L"))
    )
    (comp (ref "R19")
      (value "10k")
      (footprint "R0805")
      (description "Res Thick Film 0805 10K Ohm 1% 0.125W(1/8W) +/-100ppm/C Epoxy Pad SMD T/R")
      (fields
        (field (name "MANUFACTURER") "Yageo Group")
        (field (name "MANUFACTURER PART NUMBER") "RC0805FR-0710KL")
      )
      (libsource (lib "28Pins_Project_V1I1") (part "RC0805FR-0710KL"))
    )
    (comp (ref "R20")
      (value "1M")
      (footprint "R0805")
      (description "125mW Thick Film Resistors 150V ±100ppm/℃ ±1% 1MΩ 0805 Chip Resistor - Surface Mount ROHS")
      (fields
        (field (name "MANUFACTURER") "Yageo Group")
        (field (name "MANUFACTURER PART NUMBER") "RC0805FR-071ML")
      )
      (libsource (lib "28Pins_Project_V1I1") (part "RC0805FR-071ML"))
    )
    (comp (ref "R21")
      (value "10k")
      (footprint "R0805")
      (description "Res Thick Film 0805 10K Ohm 1% 0.125W(1/8W) +/-100ppm/C Epoxy Pad SMD T/R")
      (fields
        (field (name "MANUFACTURER") "Yageo Group")
        (field (name "MANUFACTURER PART NUMBER") "RC0805FR-0710KL")
      )
      (libsource (lib "28Pins_Project_V1I1") (part "RC0805FR-0710KL"))
    )
    (comp (ref "R22")
      (value "10k")
      (footprint "R0805")
      (description "Res Thick Film 0805 10K Ohm 1% 0.125W(1/8W) +/-100ppm/C Epoxy Pad SMD T/R")
      (fields
        (field (name "MANUFACTURER") "Yageo Group")
        (field (name "MANUFACTURER PART NUMBER") "RC0805FR-0710KL")
      )
      (libsource (lib "28Pins_Project_V1I1") (part "RC0805FR-0710KL"))
    )
    (comp (ref "R23")
      (value "10k")
      (footprint "R0805")
      (description "Res Thick Film 0805 10K Ohm 1% 0.125W(1/8W) +/-100ppm/C Epoxy Pad SMD T/R")
      (fields
        (field (name "MANUFACTURER") "Yageo Group")
        (field (name "MANUFACTURER PART NUMBER") "RC0805FR-0710KL")
      )
      (libsource (lib "28Pins_Project_V1I1") (part "RC0805FR-0710KL"))
    )
    (comp (ref "R24")
      (value "10k")
      (footprint "R0805")
      (description "Res Thick Film 0805 10K Ohm 1% 0.125W(1/8W) +/-100ppm/C Epoxy Pad SMD T/R")
      (fields
        (field (name "MANUFACTURER") "Yageo Group")
        (field (name "MANUFACTURER PART NUMBER") "RC0805FR-0710KL")
      )
      (libsource (lib "28Pins_Project_V1I1") (part "RC0805FR-0710KL"))
    )
    (comp (ref "R25")
      (value "22R")
      (footprint "R0805")
      (description "125mW Thick Film Resistors 150V ±1% ±200ppm/℃ 2.2Ω 0805 Chip Resistor - Surface Mount ROHS")
      (fields
        (field (name "MANUFACTURER") "Yageo Group")
        (field (name "MANUFACTURER PART NUMBER") "RC0805FR-072R2L")
      )
      (libsource (lib "28Pins_Project_V1I1") (part "RC0805FR-072R2L"))
    )
    (comp (ref "R26")
      (value "560R")
      (footprint "R0805")
      (description "Res Thick Film 0805 560 Ohm 1% 0.125W(1/8W) ±100ppm/C Pad SMD T/R")
      (fields
        (field (name "MANUFACTURER") "Yageo Group")
        (field (name "MANUFACTURER PART NUMBER") "RC0805FR-07560RL")
      )
      (libsource (lib "28Pins_Project_V1I1") (part "RC0805FR-07560RL"))
    )
    (comp (ref "R27")
      (value "22R")
      (footprint "R0805")
      (description "125mW Thick Film Resistors 150V ±1% ±200ppm/℃ 2.2Ω 0805 Chip Resistor - Surface Mount ROHS")
      (fields
        (field (name "MANUFACTURER") "Yageo Group")
        (field (name "MANUFACTURER PART NUMBER") "RC0805FR-072R2L")
      )
      (libsource (lib "28Pins_Project_V1I1") (part "RC0805FR-072R2L"))
    )
    (comp (ref "R28")
      (value "22R")
      (footprint "R0805")
      (description "125mW Thick Film Resistors 150V ±1% ±200ppm/℃ 2.2Ω 0805 Chip Resistor - Surface Mount ROHS")
      (fields
        (field (name "MANUFACTURER") "Yageo Group")
        (field (name "MANUFACTURER PART NUMBER") "RC0805FR-072R2L")
      )
      (libsource (lib "28Pins_Project_V1I1") (part "RC0805FR-072R2L"))
    )
    (comp (ref "R29")
      (value "10k")
      (footprint "R0805")
      (description "Res Thick Film 0805 10K Ohm 1% 0.125W(1/8W) +/-100ppm/C Epoxy Pad SMD T/R")
      (fields
        (field (name "MANUFACTURER") "Yageo Group")
        (field (name "MANUFACTURER PART NUMBER") "RC0805FR-0710KL")
      )
      (libsource (lib "28Pins_Project_V1I1") (part "RC0805FR-0710KL"))
    )
    (comp (ref "R30")
      (value "22R")
      (footprint "R0805")
      (description "125mW Thick Film Resistors 150V ±1% ±200ppm/℃ 2.2Ω 0805 Chip Resistor - Surface Mount ROHS")
      (fields
        (field (name "MANUFACTURER") "Yageo Group")
        (field (name "MANUFACTURER PART NUMBER") "RC0805FR-072R2L")
      )
      (libsource (lib "28Pins_Project_V1I1") (part "RC0805FR-072R2L"))
    )
    (comp (ref "R31")
      (value "10k")
      (footprint "R0805")
      (description "Res Thick Film 0805 10K Ohm 1% 0.125W(1/8W) +/-100ppm/C Epoxy Pad SMD T/R")
      (fields
        (field (name "MANUFACTURER") "Yageo Group")
        (field (name "MANUFACTURER PART NUMBER") "RC0805FR-0710KL")
      )
      (libsource (lib "28Pins_Project_V1I1") (part "RC0805FR-0710KL"))
    )
    (comp (ref "R32")
      (value "10k")
      (footprint "R0805")
      (description "Res Thick Film 0805 10K Ohm 1% 0.125W(1/8W) +/-100ppm/C Epoxy Pad SMD T/R")
      (fields
        (field (name "MANUFACTURER") "Yageo Group")
        (field (name "MANUFACTURER PART NUMBER") "RC0805FR-0710KL")
      )
      (libsource (lib "28Pins_Project_V1I1") (part "RC0805FR-0710KL"))
    )
    (comp (ref "SCKT FOR U1")
      (value "28-DIP Socket")
      (footprint "28_DIP_7.62mm_SOCKET")
      (description "IC Socket, DIP28, 28 Contact(s), 2.54mm Term Pitch, 7.62mm Row Spacing, Solder")
      (fields (field (name "MANUFACTURER") "3M") (field (name "MANUFACTURER PART NUMBER") "4828-3004-CP"))
      (libsource (lib "28Pins_Project_V1I1") (part "4828-3004-CP"))
    )
    (comp (ref "SW1")
      (value "1825910-6")
      (footprint "1825910-6")
      (description "Switch Tactile OFF (ON) SPST Round Button PC Pins 0.05A 24VDC 1.57N Thru-Hole Loose")
      (fields (field (name "MANUFACTURER") "TE Connectivity"))
      (libsource (lib "") (part "1825910-6_1"))
    )
    (comp (ref "SW2")
      (value "1825910-6")
      (footprint "1825910-6")
      (description "Switch Tactile OFF (ON) SPST Round Button PC Pins 0.05A 24VDC 1.57N Thru-Hole Loose")
      (fields (field (name "MANUFACTURER") "TE Connectivity"))
      (libsource (lib "") (part "1825910-6_1"))
    )
    (comp (ref "SW3")
      (value "1825910-6")
      (footprint "1825910-6")
      (description "Switch Tactile OFF (ON) SPST Round Button PC Pins 0.05A 24VDC 1.57N Thru-Hole Loose")
      (fields (field (name "MANUFACTURER") "TE Connectivity"))
      (libsource (lib "") (part "1825910-6_1"))
    )
    (comp (ref "SW4")
      (value "1825910-6")
      (footprint "1825910-6")
      (description "Switch Tactile OFF (ON) SPST Round Button PC Pins 0.05A 24VDC 1.57N Thru-Hole Loose")
      (fields (field (name "MANUFACTURER") "TE Connectivity"))
      (libsource (lib "28Pins_Project_V1I1") (part "1825910-6"))
    )
    (comp (ref "U1")
      (value "ATMEGA16U2-AU")
      (footprint "TQFP32")
      (description "Risc Microcontroller, 8-BIT, Flash, AVR Risc Cpu, 16MHZ, Cmos, PQFP32")
      (fields (field (name "MANUFACTURER") "Microchip"))
      (libsource (lib "28Pins_Project_V1I1") (part "ATMEGA16U2-AU"))
    )
    (comp (ref "U2")
      (value "296-29202-1-ND")
      (footprint "DBV_SOT_23_5")
      (description "1-ch, 2-input 2-V to 5.5-V high-speed (9 ns) AND gate with open-drain outputs 5-SOT-23 -55 to 125")
      (fields
        (field (name "MANUFACTURER") "Texas Instruments")
        (field (name "MANUFACTURER PART NUMBER") "SN74AHC1G09DBVR")
      )
      (libsource (lib "28Pins_Project_V1I1") (part "SN74AHC1G09DBVR"))
    )
    (comp (ref "U3")
      (value "TL1963A-33DCQR")
      (footprint "DCQ")
      (description "LDO Regulator Pos 3.3V 1.5A 6-Pin(5+Tab) SOT-223 T/R")
      (fields (field (name "MANUFACTURER") "Texas Instruments"))
      (libsource (lib "28Pins_Project_V1I1") (part "TL1963A-33DCQR"))
    )
    (comp (ref "U4")
      (value "ATMEGA328P-PU")
      (footprint "28_DIP_7.62mm - duplicate")
      (description "Microchip - ATMEGA328P-PU - Microcontroller Mcu, 8 Bit, Atmega, 20MHZ, DIP-28")
      (fields (field (name "MANUFACTURER") "Microchip"))
      (libsource (lib "28Pins_Project_V1I1") (part "ATMEGA328P-PU"))
    )
    (comp (ref "U5")
      (value "296-29202-1-ND")
      (footprint "DBV_SOT_23_5")
      (description "1-ch, 2-input 2-V to 5.5-V high-speed (9 ns) AND gate with open-drain outputs 5-SOT-23 -55 to 125")
      (fields
        (field (name "MANUFACTURER") "Texas Instruments")
        (field (name "MANUFACTURER PART NUMBER") "SN74AHC1G09DBVR")
      )
      (libsource (lib "28Pins_Project_V1I1") (part "SN74AHC1G09DBVR"))
    )
    (comp (ref "U6")
      (value "296-29202-1-ND")
      (footprint "DBV_SOT_23_5")
      (description "1-ch, 2-input 2-V to 5.5-V high-speed (9 ns) AND gate with open-drain outputs 5-SOT-23 -55 to 125")
      (fields
        (field (name "MANUFACTURER") "Texas Instruments")
        (field (name "MANUFACTURER PART NUMBER") "SN74AHC1G09DBVR")
      )
      (libsource (lib "28Pins_Project_V1I1") (part "SN74AHC1G09DBVR"))
    )
    (comp (ref "U7")
      (value "296-29202-1-ND")
      (footprint "DBV_SOT_23_5")
      (description "1-ch, 2-input 2-V to 5.5-V high-speed (9 ns) AND gate with open-drain outputs 5-SOT-23 -55 to 125")
      (fields
        (field (name "MANUFACTURER") "Texas Instruments")
        (field (name "MANUFACTURER PART NUMBER") "SN74AHC1G09DBVR")
      )
      (libsource (lib "28Pins_Project_V1I1") (part "SN74AHC1G09DBVR"))
    )
    (comp (ref "U8")
      (value "ESP32-WROOM-32E-N4")
      (footprint "ESP32-WROOM-32E-N4")
      (description "WLAN+BT Module 2412MHz to 2484MHz 47-Pin SMD Module")
      (fields (field (name "MANUFACTURER") "Espressif Systems"))
      (libsource (lib "28Pins_Project_V1I1") (part "ESP32-WROOM-32E-N4"))
    )
    (comp (ref "U9")
      (value "AP2112K-3.3TRG1")
      (footprint "AP2112K-3.3TRG1")
      (description "AP2112 Series 0.6 A 3.3 V Fixed Output SMT LDO Linear Regulator - SOT23-5")
      (fields (field (name "MANUFACTURER") "Diodes Inc."))
      (libsource (lib "28Pins_Project_V1I1") (part "AP2112K-3.3TRG1"))
    )
    (comp (ref "U10")
      (value "296-29202-1-ND")
      (footprint "DBV_SOT_23_5")
      (description "1-ch, 2-input 2-V to 5.5-V high-speed (9 ns) AND gate with open-drain outputs 5-SOT-23 -55 to 125")
      (fields
        (field (name "MANUFACTURER") "Texas Instruments")
        (field (name "MANUFACTURER PART NUMBER") "SN74AHC1G09DBVR")
      )
      (libsource (lib "28Pins_Project_V1I1") (part "SN74AHC1G09DBVR"))
    )
    (comp (ref "Y1")
      (value "ABM7-16.000MHZ-D2Y-T")
      (footprint "ABM7_v1_1_BIG")
      (description "Crystal 16MHz ±20ppm (Tol) ±30ppm (Stability) 18pF FUND 50Ohm 2-Pin Mini-CSMD T/R")
      (fields (field (name "MANUFACTURER") "Abracon") (field (name "TOLERANCE") "0.002%"))
      (libsource (lib "28Pins_Project_V1I1") (part "ABM7-16.000MHZ-D2Y-T"))
    )
    (comp (ref "Y2")
      (value "ABM7-16.000MHZ-D2Y-T")
      (footprint "ABM7_v1_1_BIG")
      (description "Crystal 16MHz ±20ppm (Tol) ±30ppm (Stability) 18pF FUND 50Ohm 2-Pin Mini-CSMD T/R")
      (fields (field (name "MANUFACTURER") "Abracon") (field (name "TOLERANCE") "0.002%"))
      (libsource (lib "28Pins_Project_V1I1") (part "ABM7-16.000MHZ-D2Y-T"))
    )
    (comp (ref "Z1")
      (value "CG0603MLC-05E")
      (footprint "R0603")
      (description "ESD Suppressor Multilayer Varistor 5V Automotive 2-Pin Case 0603(1608Metric) T/R")
      (fields (field (name "MANUFACTURER") "Bourns") (field (name "VOLTAGE") "5V"))
      (libsource (lib "28Pins_Project_V1I1") (part "CG0603MLC-05E"))
    )
    (comp (ref "Z2")
      (value "CG0603MLC-05E")
      (footprint "R0603")
      (description "ESD Suppressor Multilayer Varistor 5V Automotive 2-Pin Case 0603(1608Metric) T/R")
      (fields (field (name "MANUFACTURER") "Bourns") (field (name "VOLTAGE") "5V"))
      (libsource (lib "28Pins_Project_V1I1") (part "CG0603MLC-05E"))
    )
  )
  (nets
    (net (code "1") (name "+3.3V") (class "Default")
      (node (ref "C18") (pin "2") (pinfunction "2_2") (pintype "passive"))
      (node (ref "C3") (pin "2") (pinfunction "2_2") (pintype "passive"))
      (node (ref "J1") (pin "4") (pinfunction "4_4") (pintype "passive"))
      (node (ref "JP3") (pin "3") (pinfunction "3_3") (pintype "passive"))
      (node (ref "R16") (pin "2") (pinfunction "2_2") (pintype "passive"))
      (node (ref "U3") (pin "4") (pinfunction "OUT_4") (pintype "passive"))
      (node (ref "U3") (pin "5") (pinfunction "SENCE/ADJ_5") (pintype "passive"))
    )
    (net (code "2") (name "+3.3V_ESP") (class "Default")
      (node (ref "C34") (pin "2") (pinfunction "2_2") (pintype "passive"))
      (node (ref "C38") (pin "2") (pinfunction "2_2") (pintype "passive"))
      (node (ref "C42") (pin "2") (pinfunction "2_2") (pintype "passive"))
      (node (ref "D7") (pin "1") (pinfunction "Cathode_1") (pintype "passive"))
      (node (ref "FB4") (pin "1") (pinfunction "1_1") (pintype "passive"))
      (node (ref "R29") (pin "2") (pinfunction "2_2") (pintype "passive"))
      (node (ref "R31") (pin "2") (pinfunction "2_2") (pintype "passive"))
      (node (ref "R32") (pin "2") (pinfunction "2_2") (pintype "passive"))
      (node (ref "U10") (pin "5") (pinfunction "5_5") (pintype "passive"))
      (node (ref "U9") (pin "5") (pinfunction "VOUT_5") (pintype "passive"))
    )
    (net (code "3") (name "+5V") (class "Default")
      (node (ref "C1") (pin "2") (pinfunction "2_2") (pintype "passive"))
      (node (ref "C13") (pin "1") (pinfunction "1_1") (pintype "passive"))
      (node (ref "C17") (pin "2") (pinfunction "2_2") (pintype "passive"))
      (node (ref "C37") (pin "2") (pinfunction "2_2") (pintype "passive"))
      (node (ref "C9") (pin "2") (pinfunction "2_2") (pintype "passive"))
      (node (ref "J1") (pin "5") (pinfunction "5_5") (pintype "passive"))
      (node (ref "J5") (pin "1") (pinfunction "1_1") (pintype "passive"))
      (node (ref "JP3") (pin "1") (pinfunction "1_1") (pintype "passive"))
      (node (ref "L1") (pin "2") (pinfunction "_2_2") (pintype "passive"))
      (node (ref "R15") (pin "1") (pinfunction "1_1") (pintype "passive"))
      (node (ref "U1") (pin "31") (pinfunction "UVCC_31") (pintype "passive"))
      (node (ref "U3") (pin "1") (pinfunction "~{SHD}N_1") (pintype "passive"))
      (node (ref "U3") (pin "2") (pinfunction "IN_2") (pintype "passive"))
      (node (ref "U9") (pin "1") (pinfunction "VIN_1") (pintype "passive"))
      (node (ref "U9") (pin "3") (pinfunction "EN_3") (pintype "passive"))
    )
    (net (code "4") (name "+5{slash}3.3V") (class "Default")
      (node (ref "C11") (pin "2") (pinfunction "2_2") (pintype "passive"))
      (node (ref "C19") (pin "2") (pinfunction "2_2") (pintype "passive"))
      (node (ref "C2") (pin "2") (pinfunction "2_2") (pintype "passive"))
      (node (ref "C28") (pin "2") (pinfunction "2_2") (pintype "passive"))
      (node (ref "C29") (pin "2") (pinfunction "2_2") (pintype "passive"))
      (node (ref "C30") (pin "2") (pinfunction "2_2") (pintype "passive"))
      (node (ref "C4") (pin "2") (pinfunction "2_2") (pintype "passive"))
      (node (ref "C5") (pin "2") (pinfunction "2_2") (pintype "passive"))
      (node (ref "D5") (pin "1") (pinfunction "Cathode_1") (pintype "passive"))
      (node (ref "D6") (pin "1") (pinfunction "Cathode_1") (pintype "passive"))
      (node (ref "FB1") (pin "1") (pinfunction "1_1") (pintype "passive"))
      (node (ref "FB2") (pin "1") (pinfunction "1_1") (pintype "passive"))
      (node (ref "FB3") (pin "1") (pinfunction "1_1") (pintype "passive"))
      (node (ref "J1") (pin "2") (pinfunction "2_2") (pintype "passive"))
      (node (ref "J3") (pin "2") (pinfunction "2_2") (pintype "passive"))
      (node (ref "J6") (pin "2") (pinfunction "2_2") (pintype "passive"))
      (node (ref "JP3") (pin "2") (pinfunction "2_2") (pintype "passive"))
      (node (ref "R1") (pin "2") (pinfunction "2_2") (pintype "passive"))
      (node (ref "R15") (pin "2") (pinfunction "2_2") (pintype "passive"))
      (node (ref "R16") (pin "1") (pinfunction "1_1") (pintype "passive"))
      (node (ref "R19") (pin "2") (pinfunction "2_2") (pintype "passive"))
      (node (ref "R2") (pin "2") (pinfunction "2_2") (pintype "passive"))
      (node (ref "R21") (pin "2") (pinfunction "2_2") (pintype "passive"))
      (node (ref "R22") (pin "2") (pinfunction "2_2") (pintype "passive"))
      (node (ref "R23") (pin "2") (pinfunction "2_2") (pintype "passive"))
      (node (ref "R24") (pin "2") (pinfunction "2_2") (pintype "passive"))
      (node (ref "R3") (pin "2") (pinfunction "2_2") (pintype "passive"))
      (node (ref "R4") (pin "2") (pinfunction "2_2") (pintype "passive"))
      (node (ref "R5") (pin "2") (pinfunction "2_2") (pintype "passive"))
      (node (ref "R7") (pin "2") (pinfunction "2_2") (pintype "passive"))
      (node (ref "U2") (pin "5") (pinfunction "5_5") (pintype "passive"))
      (node (ref "U5") (pin "5") (pinfunction "5_5") (pintype "passive"))
      (node (ref "U6") (pin "5") (pinfunction "5_5") (pintype "passive"))
      (node (ref "U7") (pin "5") (pinfunction "5_5") (pintype "passive"))
    )
    (net (code "5") (name "+AREF") (class "Default")
      (node (ref "C20") (pin "2") (pinfunction "2_2") (pintype "passive"))
      (node (ref "C25") (pin "2") (pinfunction "2_2") (pintype "passive"))
      (node (ref "J8") (pin "8") (pinfunction "8_8") (pintype "passive"))
      (node (ref "U4") (pin "21") (pinfunction "AREF_21") (pintype "passive"))
    )
    (net (code "6") (name "/+3V3_16U2_UCAP") (class "Default")
      (node (ref "C10") (pin "2") (pinfunction "2_2") (pintype "passive"))
      (node (ref "R6") (pin "1") (pinfunction "1_1") (pintype "passive"))
      (node (ref "U1") (pin "27") (pinfunction "UCAP_27") (pintype "passive"))
    )
    (net (code "7") (name "/+3V3_ESP_VCC") (class "Default")
      (node (ref "C35") (pin "2") (pinfunction "2_2") (pintype "passive"))
      (node (ref "C36") (pin "2") (pinfunction "2_2") (pintype "passive"))
      (node (ref "FB4") (pin "2") (pinfunction "2_2") (pintype "passive"))
      (node (ref "U8") (pin "2") (pinfunction "3V3_2") (pintype "power_in"))
    )
    (net (code "8") (name "/+5V_USB") (class "Default")
      (node (ref "C12") (pin "1") (pinfunction "1_1") (pintype "passive"))
      (node (ref "J4") (pin "1") (pinfunction "1_1") (pintype "passive"))
      (node (ref "L1") (pin "1") (pinfunction "_1_1") (pintype "passive"))
    )
    (net (code "9") (name "/+5{slash}3V3_16U2") (class "Default")
      (node (ref "C6") (pin "2") (pinfunction "2_2") (pintype "passive"))
      (node (ref "C7") (pin "2") (pinfunction "2_2") (pintype "passive"))
      (node (ref "C8") (pin "2") (pinfunction "2_2") (pintype "passive"))
      (node (ref "FB1") (pin "2") (pinfunction "2_2") (pintype "passive"))
      (node (ref "R6") (pin "2") (pinfunction "2_2") (pintype "passive"))
      (node (ref "U1") (pin "32") (pinfunction "AVCC_32") (pintype "passive"))
      (node (ref "U1") (pin "4") (pinfunction "VCC_4") (pintype "passive"))
    )
    (net (code "10") (name "/+5{slash}3V3_328P_AVCC") (class "Default")
      (node (ref "C23") (pin "2") (pinfunction "2_2") (pintype "passive"))
      (node (ref "C24") (pin "2") (pinfunction "2_2") (pintype "passive"))
      (node (ref "FB3") (pin "2") (pinfunction "2_2") (pintype "passive"))
      (node (ref "U4") (pin "20") (pinfunction "AVCC_20") (pintype "passive"))
    )
    (net (code "11") (name "/+5{slash}3V3_328P_VCC") (class "Default")
      (node (ref "C21") (pin "2") (pinfunction "2_2") (pintype "passive"))
      (node (ref "C22") (pin "2") (pinfunction "2_2") (pintype "passive"))
      (node (ref "FB2") (pin "2") (pinfunction "2_2") (pintype "passive"))
      (node (ref "U4") (pin "7") (pinfunction "VCC_7") (pintype "passive"))
    )
    (net (code "12") (name "/16U2PROG_328P_RESETn") (class "Default")
      (node (ref "JP2") (pin "2") (pinfunction "2_2") (pintype "passive"))
      (node (ref "R3") (pin "1") (pinfunction "1_1") (pintype "passive"))
      (node (ref "U1") (pin "13") (pinfunction "~{(CST}/~{_HWB}_/_AIN6_/_T0_/_INT7)_PD7_13") (pintype "passive"))
    )
    (net (code "13") (name "/16U2_16MHz_XTAL1") (class "Default")
      (node (ref "C15") (pin "2") (pinfunction "2_2") (pintype "passive"))
      (node (ref "R13") (pin "1") (pinfunction "1_1") (pintype "passive"))
      (node (ref "U1") (pin "1") (pinfunction "XTAL1_1") (pintype "passive"))
      (node (ref "Y1") (pin "1") (pinfunction "1_1") (pintype "passive"))
    )
    (net (code "14") (name "/16U2_16MHz_XTAL2") (class "Default")
      (node (ref "C14") (pin "2") (pinfunction "2_2") (pintype "passive"))
      (node (ref "R13") (pin "2") (pinfunction "2_2") (pintype "passive"))
      (node (ref "U1") (pin "2") (pinfunction "(PC0)_XTAL2_2") (pintype "passive"))
      (node (ref "Y1") (pin "2") (pinfunction "2_2") (pintype "passive"))
    )
    (net (code "15") (name "/16U2_BUF_RESETn") (class "Default")
      (node (ref "C33") (pin "2") (pinfunction "2_2") (pintype "passive"))
      (node (ref "R28") (pin "2") (pinfunction "2_2") (pintype "passive"))
      (node (ref "U7") (pin "1") (pinfunction "1_1") (pintype "passive"))
      (node (ref "U7") (pin "2") (pinfunction "2_2") (pintype "passive"))
    )
    (net (code "16") (name "/16U2_HDR_RESETn") (class "Default")
      (node (ref "J3") (pin "5") (pinfunction "5_5") (pintype "passive"))
      (node (ref "JP1") (pin "3") (pinfunction "3_3") (pintype "passive"))
    )
    (net (code "17") (name "/16U2_MISO") (class "Default")
      (node (ref "J3") (pin "1") (pinfunction "1_1") (pintype "passive"))
      (node (ref "U1") (pin "17") (pinfunction "PB3_(PDO_/_MISO_/_PCINT3)_17") (pintype "passive"))
    )
    (net (code "18") (name "/16U2_MOSI") (class "Default")
      (node (ref "J3") (pin "4") (pinfunction "4_4") (pintype "passive"))
      (node (ref "U1") (pin "16") (pinfunction "(PDI_/_MOSI_/_PCINT2)_PB2_16") (pintype "passive"))
    )
    (net (code "19") (name "/16U2_PB4") (class "Default")
      (node (ref "J2") (pin "1") (pinfunction "1_1") (pintype "passive"))
      (node (ref "JP1") (pin "2") (pinfunction "2_2") (pintype "passive"))
      (node (ref "U1") (pin "18") (pinfunction "PB4_(T1_/_PCINT4)_18") (pintype "passive"))
    )
    (net (code "20") (name "/16U2_PB5") (class "Default")
      (node (ref "J2") (pin "3") (pinfunction "3_3") (pintype "passive"))
      (node (ref "U1") (pin "19") (pinfunction "PB5_(PCINT5)_19") (pintype "passive"))
    )
    (net (code "21") (name "/16U2_PB6") (class "Default")
      (node (ref "J2") (pin "2") (pinfunction "2_2") (pintype "passive"))
      (node (ref "U1") (pin "20") (pinfunction "PB6_(PCINT6)_20") (pintype "passive"))
    )
    (net (code "22") (name "/16U2_PB7") (class "Default")
      (node (ref "J2") (pin "4") (pinfunction "4_4") (pintype "passive"))
      (node (ref "U1") (pin "21") (pinfunction "PB7_(PCINT7_/_OC.0A_/_OC.1C)_21") (pintype "passive"))
    )
    (net (code "23") (name "/16U2_RESETn") (class "Default")
      (node (ref "JP1") (pin "4") (pinfunction "4_4") (pintype "passive"))
      (node (ref "R7") (pin "1") (pinfunction "1_1") (pintype "passive"))
      (node (ref "U1") (pin "24") (pinfunction "~{Reset}_(PC1_/_dW)_24") (pintype "passive"))
      (node (ref "U7") (pin "4") (pinfunction "4_4") (pintype "passive"))
    )
    (net (code "24") (name "/16U2_RXD") (class "Default")
      (node (ref "R14") (pin "1") (pinfunction "1_1") (pintype "passive"))
      (node (ref "U1") (pin "8") (pinfunction "(RXD1_/_AIN1_/_INT2)_PD2_8") (pintype "passive"))
    )
    (net (code "25") (name "/16U2_RX_LED") (class "Default")
      (node (ref "D2") (pin "1") (pinfunction "Cathode_1") (pintype "passive"))
      (node (ref "U1") (pin "10") (pinfunction "(INT5/_AIN3)_PD4_10") (pintype "passive"))
    )
    (net (code "26") (name "/16U2_SCLK") (class "Default")
      (node (ref "J3") (pin "3") (pinfunction "3_3") (pintype "passive"))
      (node (ref "R8") (pin "2") (pinfunction "2_2") (pintype "passive"))
    )
    (net (code "27") (name "/16U2_SCLK_R") (class "Default")
      (node (ref "R8") (pin "1") (pinfunction "1_1") (pintype "passive"))
      (node (ref "U1") (pin "15") (pinfunction "(SCLK_/_PCINT1)_PB1_15") (pintype "passive"))
    )
    (net (code "28") (name "/16U2_TXD") (class "Default")
      (node (ref "R12") (pin "1") (pinfunction "1_1") (pintype "passive"))
      (node (ref "U1") (pin "9") (pinfunction "(TXD1_/_INT3)_PD3_9") (pintype "passive"))
    )
    (net (code "29") (name "/16U2_TX_LED") (class "Default")
      (node (ref "D1") (pin "1") (pinfunction "Cathode_1") (pintype "passive"))
      (node (ref "U1") (pin "11") (pinfunction "(XCK_AIN4_/_PCINT12)_PD5_11") (pintype "passive"))
    )
    (net (code "30") (name "/328P_16MHz_XTAL1") (class "Default")
      (node (ref "C27") (pin "2") (pinfunction "2_2") (pintype "passive"))
      (node (ref "R20") (pin "1") (pinfunction "1_1") (pintype "passive"))
      (node (ref "U4") (pin "9") (pinfunction "(PCINT6/XTAL1/TOSC1)_PB6_9") (pintype "passive"))
      (node (ref "Y2") (pin "1") (pinfunction "1_1") (pintype "passive"))
    )
    (net (code "31") (name "/328P_16MHz_XTAL2") (class "Default")
      (node (ref "C26") (pin "2") (pinfunction "2_2") (pintype "passive"))
      (node (ref "R20") (pin "2") (pinfunction "2_2") (pintype "passive"))
      (node (ref "U4") (pin "10") (pinfunction "(PCINT7/XTAL2/TOSC2)_PB7_10") (pintype "passive"))
      (node (ref "Y2") (pin "2") (pinfunction "2_2") (pintype "passive"))
    )
    (net (code "32") (name "/328P_AUTORESETn") (class "Default")
      (node (ref "C16") (pin "1") (pinfunction "1_1") (pintype "passive"))
      (node (ref "R21") (pin "1") (pinfunction "1_1") (pintype "passive"))
      (node (ref "U5") (pin "1") (pinfunction "1_1") (pintype "passive"))
    )
    (net (code "33") (name "/328P_BUF_RESETn") (class "Default")
      (node (ref "C31") (pin "2") (pinfunction "2_2") (pintype "passive"))
      (node (ref "R25") (pin "2") (pinfunction "2_2") (pintype "passive"))
      (node (ref "U5") (pin "2") (pinfunction "2_2") (pintype "passive"))
    )
    (net (code "34") (name "/328P_RESETn") (class "Default")
      (node (ref "J1") (pin "3") (pinfunction "3_3") (pintype "passive"))
      (node (ref "J6") (pin "5") (pinfunction "5_5") (pintype "passive"))
      (node (ref "JP1") (pin "1") (pinfunction "1_1") (pintype "passive"))
      (node (ref "R19") (pin "1") (pinfunction "1_1") (pintype "passive"))
      (node (ref "U4") (pin "1") (pinfunction "(PCINT14~{/RESET})_PC6_1") (pintype "passive"))
      (node (ref "U5") (pin "4") (pinfunction "4_4") (pintype "passive"))
    )
    (net (code "35") (name "/AD0") (class "Default")
      (node (ref "J9") (pin "1") (pinfunction "1_1") (pintype "passive"))
      (node (ref "U4") (pin "23") (pinfunction "PC0_(ADC0/PCINT8)_23") (pintype "passive"))
    )
    (net (code "36") (name "/AD1") (class "Default")
      (node (ref "J9") (pin "2") (pinfunction "2_2") (pintype "passive"))
      (node (ref "U4") (pin "24") (pinfunction "PC1_(ADC1/PCINT9)_24") (pintype "passive"))
    )
    (net (code "37") (name "/AD2") (class "Default")
      (node (ref "J9") (pin "3") (pinfunction "3_3") (pintype "passive"))
      (node (ref "U4") (pin "25") (pinfunction "PC2_(ADC2/PCINT10)_25") (pintype "passive"))
    )
    (net (code "38") (name "/AD3") (class "Default")
      (node (ref "J9") (pin "4") (pinfunction "4_4") (pintype "passive"))
      (node (ref "U4") (pin "26") (pinfunction "PC3_(ADC3/PCINT11)_26") (pintype "passive"))
    )
    (net (code "39") (name "/AD4{slash}SDA") (class "Default")
      (node (ref "J8") (pin "9") (pinfunction "9_9") (pintype "passive"))
      (node (ref "J9") (pin "5") (pinfunction "5_5") (pintype "passive"))
      (node (ref "U4") (pin "27") (pinfunction "PC4_(ADC4/SDA/PCINT12)_27") (pintype "passive"))
    )
    (net (code "40") (name "/AD5{slash}SDL") (class "Default")
      (node (ref "J8") (pin "10") (pinfunction "10_10") (pintype "passive"))
      (node (ref "J9") (pin "6") (pinfunction "6_6") (pintype "passive"))
      (node (ref "U4") (pin "28") (pinfunction "PC5_(ADC5/SCL/PCINT13)_28") (pintype "passive"))
    )
    (net (code "41") (name "/BUTTON_RESET_ESP") (class "Default")
      (node (ref "D7") (pin "2") (pinfunction "Anode_2") (pintype "passive"))
      (node (ref "R29") (pin "1") (pinfunction "1_1") (pintype "passive"))
      (node (ref "R30") (pin "1") (pinfunction "1_1") (pintype "passive"))
      (node (ref "SW3") (pin "1") (pinfunction "1_1") (pintype "passive"))
      (node (ref "SW3") (pin "2") (pinfunction "2_2") (pintype "passive"))
    )
    (net (code "42") (name "/BUTTON_RESETn") (class "Default")
      (node (ref "D5") (pin "2") (pinfunction "Anode_2") (pintype "passive"))
      (node (ref "R22") (pin "1") (pinfunction "1_1") (pintype "passive"))
      (node (ref "R25") (pin "1") (pinfunction "1_1") (pintype "passive"))
      (node (ref "SW1") (pin "1") (pinfunction "1_1") (pintype "passive"))
      (node (ref "SW1") (pin "2") (pinfunction "2_2") (pintype "passive"))
    )
    (net (code "43") (name "/CON_USB_N") (class "Default")
      (node (ref "J4") (pin "2") (pinfunction "2_2") (pintype "passive"))
      (node (ref "R9") (pin "1") (pinfunction "1_1") (pintype "passive"))
      (node (ref "Z1") (pin "2") (pintype "passive"))
    )
    (net (code "44") (name "/CON_USB_P") (class "Default")
      (node (ref "J4") (pin "3") (pinfunction "3_3") (pintype "passive"))
      (node (ref "R10") (pin "1") (pinfunction "1_1") (pintype "passive"))
      (node (ref "Z2") (pin "2") (pintype "passive"))
    )
    (net (code "45") (name "/ESP_BUF_RESETn") (class "Default")
      (node (ref "C39") (pin "2") (pinfunction "2_2") (pintype "passive"))
      (node (ref "R30") (pin "2") (pinfunction "2_2") (pintype "passive"))
      (node (ref "U10") (pin "1") (pinfunction "1_1") (pintype "passive"))
      (node (ref "U10") (pin "2") (pinfunction "2_2") (pintype "passive"))
    )
    (net (code "46") (name "/ESP_RESETn") (class "Default")
      (node (ref "U10") (pin "4") (pinfunction "4_4") (pintype "passive"))
      (node (ref "U8") (pin "3") (pinfunction "EN_3") (pintype "input"))
    )
    (net (code "47") (name "/IO0") (class "Default")
      (node (ref "J10") (pin "1") (pinfunction "1_1") (pintype "passive"))
      (node (ref "R12") (pin "2") (pinfunction "2_2") (pintype "passive"))
      (node (ref "U4") (pin "2") (pinfunction "(PCINT16/RXD)_PD0_2") (pintype "passive"))
    )
    (net (code "48") (name "/IO1") (class "Default")
      (node (ref "J10") (pin "2") (pinfunction "2_2") (pintype "passive"))
      (node (ref "R14") (pin "2") (pinfunction "2_2") (pintype "passive"))
      (node (ref "U4") (pin "3") (pinfunction "(PCINT17/TXD)_PD1_3") (pintype "passive"))
    )
    (net (code "49") (name "/IO2") (class "Default")
      (node (ref "J10") (pin "3") (pinfunction "3_3") (pintype "passive"))
      (node (ref "U4") (pin "4") (pinfunction "(PCINT18/INT0)_PD2_4") (pintype "passive"))
    )
    (net (code "50") (name "/IO3") (class "Default")
      (node (ref "J10") (pin "4") (pinfunction "4_4") (pintype "passive"))
      (node (ref "U4") (pin "5") (pinfunction "(PCINT19/OC2B/INT1)_PD3_5") (pintype "passive"))
    )
    (net (code "51") (name "/IO4") (class "Default")
      (node (ref "J10") (pin "5") (pinfunction "5_5") (pintype "passive"))
      (node (ref "U4") (pin "6") (pinfunction "(PCINT20/XCK/T0)_PD4_6") (pintype "passive"))
    )
    (net (code "52") (name "/IO5") (class "Default")
      (node (ref "J10") (pin "6") (pinfunction "6_6") (pintype "passive"))
      (node (ref "U4") (pin "11") (pinfunction "(PCINT21/OC0B/T1)_PD5_11") (pintype "passive"))
    )
    (net (code "53") (name "/IO6") (class "Default")
      (node (ref "J10") (pin "7") (pinfunction "7_7") (pintype "passive"))
      (node (ref "U4") (pin "12") (pinfunction "(PCINT22/OC0A/AIN0)_PD6_12") (pintype "passive"))
      (node (ref "U8") (pin "35") (pinfunction "TXD0_35") (pintype "bidirectional"))
    )
    (net (code "54") (name "/IO7") (class "Default")
      (node (ref "J10") (pin "8") (pinfunction "8_8") (pintype "passive"))
      (node (ref "U4") (pin "13") (pinfunction "(PCINT23/AIN1)_PD7_13") (pintype "passive"))
      (node (ref "U8") (pin "34") (pinfunction "RXD0_34") (pintype "bidirectional"))
    )
    (net (code "55") (name "/IO8") (class "Default")
      (node (ref "J8") (pin "1") (pinfunction "1_1") (pintype "passive"))
      (node (ref "R26") (pin "2") (pinfunction "2_2") (pintype "passive"))
      (node (ref "U4") (pin "14") (pinfunction "(PCINT0/CLKO/ICP1)_PB0_14") (pintype "passive"))
    )
    (net (code "56") (name "/IO9") (class "Default")
      (node (ref "J8") (pin "2") (pinfunction "2_2") (pintype "passive"))
      (node (ref "U4") (pin "15") (pinfunction "PB1_(OC1A/PCINT1)_15") (pintype "passive"))
    )
    (net (code "57") (name "/MISO") (class "Default")
      (node (ref "J6") (pin "1") (pinfunction "1_1") (pintype "passive"))
      (node (ref "J8") (pin "5") (pinfunction "5_5") (pintype "passive"))
      (node (ref "U4") (pin "18") (pinfunction "PB4_(MISO/PCINT4)_18") (pintype "passive"))
    )
    (net (code "58") (name "/MOSI") (class "Default")
      (node (ref "J6") (pin "4") (pinfunction "4_4") (pintype "passive"))
      (node (ref "J8") (pin "4") (pinfunction "4_4") (pintype "passive"))
      (node (ref "U4") (pin "17") (pinfunction "PB3_(MOSI/OC2A/PCINT3)_17") (pintype "passive"))
    )
    (net (code "59") (name "/SCK") (class "Default")
      (node (ref "J6") (pin "3") (pinfunction "3_3") (pintype "passive"))
      (node (ref "J8") (pin "6") (pinfunction "6_6") (pintype "passive"))
      (node (ref "R18") (pin "2") (pinfunction "2_2") (pintype "passive"))
      (node (ref "U2") (pin "1") (pinfunction "1_1") (pintype "passive"))
      (node (ref "U2") (pin "2") (pinfunction "2_2") (pintype "passive"))
    )
    (net (code "60") (name "/SCK_R") (class "Default")
      (node (ref "R18") (pin "1") (pinfunction "1_1") (pintype "passive"))
      (node (ref "U4") (pin "19") (pinfunction "PB5_(SCK/PCINT5)_19") (pintype "passive"))
    )
    (net (code "61") (name "/SS") (class "Default")
      (node (ref "J8") (pin "3") (pinfunction "3_3") (pintype "passive"))
      (node (ref "U4") (pin "16") (pinfunction "PB2_(SS/OC1B/PCINT2)_16") (pintype "passive"))
    )
    (net (code "62") (name "/USB_N") (class "Default")
      (node (ref "R9") (pin "2") (pinfunction "2_2") (pintype "passive"))
      (node (ref "U1") (pin "30") (pinfunction "D-_30") (pintype "passive"))
    )
    (net (code "63") (name "/USB_P") (class "Default")
      (node (ref "R10") (pin "2") (pinfunction "2_2") (pintype "passive"))
      (node (ref "U1") (pin "29") (pinfunction "D+_29") (pintype "passive"))
    )
    (net (code "64") (name "/USER_BUTTON") (class "Default")
      (node (ref "R23") (pin "1") (pinfunction "1_1") (pintype "passive"))
      (node (ref "R27") (pin "1") (pinfunction "1_1") (pintype "passive"))
      (node (ref "SW2") (pin "1") (pinfunction "1_1") (pintype "passive"))
      (node (ref "SW2") (pin "2") (pinfunction "2_2") (pintype "passive"))
    )
    (net (code "65") (name "/USER_BUTTON_BUF") (class "Default")
      (node (ref "C32") (pin "2") (pinfunction "2_2") (pintype "passive"))
      (node (ref "R27") (pin "2") (pinfunction "2_2") (pintype "passive"))
      (node (ref "U6") (pin "1") (pinfunction "1_1") (pintype "passive"))
      (node (ref "U6") (pin "2") (pinfunction "2_2") (pintype "passive"))
    )
    (net (code "66") (name "GND") (class "Default")
      (node (ref "C1") (pin "1") (pinfunction "1_1") (pintype "passive"))
      (node (ref "C10") (pin "1") (pinfunction "1_1") (pintype "passive"))
      (node (ref "C11") (pin "1") (pinfunction "1_1") (pintype "passive"))
      (node (ref "C12") (pin "2") (pinfunction "_2_2") (pintype "passive"))
      (node (ref "C13") (pin "2") (pinfunction "_2_2") (pintype "passive"))
      (node (ref "C14") (pin "1") (pinfunction "1_1") (pintype "passive"))
      (node (ref "C15") (pin "1") (pinfunction "1_1") (pintype "passive"))
      (node (ref "C17") (pin "1") (pinfunction "1_1") (pintype "passive"))
      (node (ref "C18") (pin "1") (pinfunction "1_1") (pintype "passive"))
      (node (ref "C19") (pin "1") (pinfunction "1_1") (pintype "passive"))
      (node (ref "C2") (pin "1") (pinfunction "1_1") (pintype "passive"))
      (node (ref "C20") (pin "1") (pinfunction "1_1") (pintype "passive"))
      (node (ref "C21") (pin "1") (pinfunction "1_1") (pintype "passive"))
      (node (ref "C22") (pin "1") (pinfunction "1_1") (pintype "passive"))
      (node (ref "C23") (pin "1") (pinfunction "1_1") (pintype "passive"))
      (node (ref "C24") (pin "1") (pinfunction "1_1") (pintype "passive"))
      (node (ref "C25") (pin "1") (pinfunction "1_1") (pintype "passive"))
      (node (ref "C26") (pin "1") (pinfunction "1_1") (pintype "passive"))
      (node (ref "C27") (pin "1") (pinfunction "1_1") (pintype "passive"))
      (node (ref "C28") (pin "1") (pinfunction "1_1") (pintype "passive"))
      (node (ref "C29") (pin "1") (pinfunction "1_1") (pintype "passive"))
      (node (ref "C3") (pin "1") (pinfunction "1_1") (pintype "passive"))
      (node (ref "C30") (pin "1") (pinfunction "1_1") (pintype "passive"))
      (node (ref "C31") (pin "1") (pinfunction "1_1") (pintype "passive"))
      (node (ref "C32") (pin "1") (pinfunction "1_1") (pintype "passive"))
      (node (ref "C33") (pin "1") (pinfunction "1_1") (pintype "passive"))
      (node (ref "C34") (pin "1") (pinfunction "1_1") (pintype "passive"))
      (node (ref "C35") (pin "1") (pinfunction "1_1") (pintype "passive"))
      (node (ref "C36") (pin "1") (pinfunction "1_1") (pintype "passive"))
      (node (ref "C37") (pin "1") (pinfunction "1_1") (pintype "passive"))
      (node (ref "C38") (pin "1") (pinfunction "1_1") (pintype "passive"))
      (node (ref "C39") (pin "1") (pinfunction "1_1") (pintype "passive"))
      (node (ref "C4") (pin "1") (pinfunction "1_1") (pintype "passive"))
      (node (ref "C40") (pin "1") (pinfunction "1_1") (pintype "passive"))
      (node (ref "C41") (pin "1") (pinfunction "1_1") (pintype "passive"))
      (node (ref "C42") (pin "1") (pinfunction "1_1") (pintype "passive"))
      (node (ref "C5") (pin "1") (pinfunction "1_1") (pintype "passive"))
      (node (ref "C6") (pin "1") (pinfunction "1_1") (pintype "passive"))
      (node (ref "C7") (pin "1") (pinfunction "1_1") (pintype "passive"))
      (node (ref "C8") (pin "1") (pinfunction "1_1") (pintype "passive"))
      (node (ref "C9") (pin "1") (pinfunction "1_1") (pintype "passive"))
      (node (ref "D3") (pin "1") (pinfunction "Cathode_1") (pintype "passive"))
      (node (ref "J1") (pin "6") (pinfunction "6_6") (pintype "passive"))
      (node (ref "J1") (pin "7") (pinfunction "7_7") (pintype "passive"))
      (node (ref "J3") (pin "6") (pinfunction "6_6") (pintype "passive"))
      (node (ref "J4") (pin "10") (pinfunction "10_10") (pintype "passive"))
      (node (ref "J4") (pin "11") (pinfunction "11_11") (pintype "passive"))
      (node (ref "J4") (pin "5") (pinfunction "5_5") (pintype "passive"))
      (node (ref "J4") (pin "6") (pinfunction "6_6") (pintype "passive"))
      (node (ref "J4") (pin "7") (pinfunction "7_7") (pintype "passive"))
      (node (ref "J4") (pin "8") (pinfunction "8_8") (pintype "passive"))
      (node (ref "J4") (pin "9") (pinfunction "9_9") (pintype "passive"))
      (node (ref "J6") (pin "6") (pinfunction "6_6") (pintype "passive"))
      (node (ref "J7") (pin "1") (pinfunction "1_1") (pintype "passive"))
      (node (ref "J8") (pin "7") (pinfunction "7_7") (pintype "passive"))
      (node (ref "MH1") (pin "1") (pinfunction "1_1") (pintype "passive"))
      (node (ref "MH2") (pin "1") (pinfunction "1_1") (pintype "passive"))
      (node (ref "MH3") (pin "1") (pinfunction "1_1") (pintype "passive"))
      (node (ref "R11") (pin "2") (pinfunction "2_2") (pintype "passive"))
      (node (ref "R17") (pin "1") (pinfunction "1_1") (pintype "passive"))
      (node (ref "SW1") (pin "3") (pinfunction "3_3") (pintype "passive"))
      (node (ref "SW1") (pin "4") (pinfunction "4_4") (pintype "passive"))
      (node (ref "SW2") (pin "3") (pinfunction "3_3") (pintype "passive"))
      (node (ref "SW2") (pin "4") (pinfunction "4_4") (pintype "passive"))
      (node (ref "SW3") (pin "3") (pinfunction "3_3") (pintype "passive"))
      (node (ref "SW3") (pin "4") (pinfunction "4_4") (pintype "passive"))
      (node (ref "SW4") (pin "3") (pinfunction "3_3") (pintype "passive"))
      (node (ref "SW4") (pin "4") (pinfunction "4_4") (pintype "passive"))
      (node (ref "U1") (pin "28") (pinfunction "UGND_28") (pintype "passive"))
      (node (ref "U1") (pin "3") (pinfunction "GND_3") (pintype "passive"))
      (node (ref "U10") (pin "3") (pinfunction "3_3") (pintype "passive"))
      (node (ref "U2") (pin "3") (pinfunction "3_3") (pintype "passive"))
      (node (ref "U3") (pin "3") (pinfunction "GND_3") (pintype "passive"))
      (node (ref "U3") (pin "6") (pinfunction "EPAD_6") (pintype "passive"))
      (node (ref "U4") (pin "22") (pinfunction "GND_2_22") (pintype "passive"))
      (node (ref "U4") (pin "8") (pinfunction "GND_1_8") (pintype "passive"))
      (node (ref "U5") (pin "3") (pinfunction "3_3") (pintype "passive"))
      (node (ref "U6") (pin "3") (pinfunction "3_3") (pintype "passive"))
      (node (ref "U7") (pin "3") (pinfunction "3_3") (pintype "passive"))
      (node (ref "U8") (pin "1") (pinfunction "GND_1") (pintype "power_in"))
      (node (ref "U8") (pin "15") (pinfunction "GND_15") (pintype "power_in"))
      (node (ref "U8") (pin "38") (pinfunction "GND_38") (pintype "power_in"))
      (node (ref "U8") (pin "39") (pinfunction "GND_39") (pintype "power_in"))
      (node (ref "U8") (pin "40") (pinfunction "GND_40") (pintype "power_in"))
      (node (ref "U8") (pin "41") (pinfunction "GND_41") (pintype "power_in"))
      (node (ref "U8") (pin "42") (pinfunction "GND_42") (pintype "power_in"))
      (node (ref "U8") (pin "43") (pinfunction "GND_43") (pintype "power_in"))
      (node (ref "U8") (pin "44") (pinfunction "GND_44") (pintype "power_in"))
      (node (ref "U8") (pin "45") (pinfunction "GND_45") (pintype "power_in"))
      (node (ref "U8") (pin "46") (pinfunction "GND_46") (pintype "power_in"))
      (node (ref "U8") (pin "47") (pinfunction "GND_47") (pintype "power_in"))
      (node (ref "U9") (pin "2") (pinfunction "GND_2") (pintype "passive"))
      (node (ref "Z1") (pin "1") (pinfunction "1_1") (pintype "passive"))
      (node (ref "Z2") (pin "1") (pinfunction "1_1") (pintype "passive"))
    )
    (net (code "67") (name "Net-(C16-Pad2)") (class "Default")
      (node (ref "C16") (pin "2") (pinfunction "2_2") (pintype "passive"))
      (node (ref "JP2") (pin "1") (pinfunction "1_1") (pintype "passive"))
    )
    (net (code "68") (name "Net-(D1-Anode)") (class "Default")
      (node (ref "D1") (pin "2") (pinfunction "Anode_2") (pintype "passive"))
      (node (ref "R1") (pin "1") (pinfunction "1_1") (pintype "passive"))
    )
    (net (code "69") (name "Net-(D2-Anode)") (class "Default")
      (node (ref "D2") (pin "2") (pinfunction "Anode_2") (pintype "passive"))
      (node (ref "R2") (pin "1") (pinfunction "1_1") (pintype "passive"))
    )
    (net (code "70") (name "Net-(D3-Anode)") (class "Default")
      (node (ref "D3") (pin "2") (pinfunction "Anode_2") (pintype "passive"))
      (node (ref "R4") (pin "1") (pinfunction "1_1") (pintype "passive"))
    )
    (net (code "71") (name "Net-(D4-Anode)") (class "Default")
      (node (ref "D4") (pin "2") (pinfunction "Anode_2") (pintype "passive"))
      (node (ref "R5") (pin "1") (pinfunction "1_1") (pintype "passive"))
    )
    (net (code "72") (name "Net-(D4-Cathode)") (class "Default")
      (node (ref "D4") (pin "1") (pinfunction "Cathode_1") (pintype "passive"))
      (node (ref "U2") (pin "4") (pinfunction "4_4") (pintype "passive"))
    )
    (net (code "73") (name "Net-(D6-Anode)") (class "Default")
      (node (ref "D6") (pin "2") (pinfunction "Anode_2") (pintype "passive"))
      (node (ref "R24") (pin "1") (pinfunction "1_1") (pintype "passive"))
      (node (ref "R28") (pin "1") (pinfunction "1_1") (pintype "passive"))
    )
    (net (code "74") (name "Net-(J4-Pad4)") (class "Default")
      (node (ref "J4") (pin "4") (pinfunction "4_4") (pintype "passive"))
      (node (ref "R11") (pin "1") (pinfunction "1_1") (pintype "passive"))
    )
    (net (code "75") (name "Net-(JP2-Pad3)") (class "Default")
      (node (ref "JP2") (pin "3") (pinfunction "3_3") (pintype "passive"))
      (node (ref "R17") (pin "2") (pinfunction "2_2") (pintype "passive"))
    )
    (net (code "76") (name "Net-(R26-Pad1)") (class "Default")
      (node (ref "R26") (pin "1") (pinfunction "1_1") (pintype "passive"))
      (node (ref "U6") (pin "4") (pinfunction "4_4") (pintype "passive"))
    )
    (net (code "77") (name "Net-(U8-IO0)") (class "Default")
      (node (ref "C40") (pin "2") (pinfunction "2_2") (pintype "passive"))
      (node (ref "R31") (pin "1") (pinfunction "1_1") (pintype "passive"))
      (node (ref "SW4") (pin "1") (pinfunction "1_1") (pintype "passive"))
      (node (ref "SW4") (pin "2") (pinfunction "2_2") (pintype "passive"))
      (node (ref "U8") (pin "25") (pinfunction "IO0_25") (pintype "bidirectional"))
    )
    (net (code "78") (name "Net-(U8-IO2)") (class "Default")
      (node (ref "C41") (pin "2") (pinfunction "2_2") (pintype "passive"))
      (node (ref "R32") (pin "1") (pinfunction "1_1") (pintype "passive"))
      (node (ref "U8") (pin "24") (pinfunction "IO2_24") (pintype "bidirectional"))
    )
    (net (code "79") (name "unconnected-(J1-Pad1)") (class "Default")
      (node (ref "J1") (pin "1") (pinfunction "1_1") (pintype "passive+no_connect"))
    )
    (net (code "80") (name "unconnected-(J1-Pad8)") (class "Default")
      (node (ref "J1") (pin "8") (pinfunction "8_8") (pintype "passive+no_connect"))
    )
    (net (code "81") (name "unconnected-(MH4-Pad1)") (class "Default")
      (node (ref "MH4") (pin "1") (pinfunction "1_1") (pintype "passive+no_connect"))
    )
    (net (code "82") (name "unconnected-(U1-(AIN0_{slash}_INT1)_PD1-Pad7)") (class "Default")
      (node (ref "U1") (pin "7") (pinfunction "(AIN0_/_INT1)_PD1_7") (pintype "passive+no_connect"))
    )
    (net (code "83") (name "unconnected-(U1-(OC.0B_{slash}_INT0)_PD0-Pad6)") (class "Default")
      (node (ref "U1") (pin "6") (pinfunction "(OC.0B_/_INT0)_PD0_6") (pintype "passive+no_connect"))
    )
    (net (code "84") (name "unconnected-(U1-(PCINT11_{slash}AIN2_)_PC2-Pad5)") (class "Default")
      (node (ref "U1") (pin "5") (pinfunction "(PCINT11_/AIN2_)_PC2_5") (pintype "passive+no_connect"))
    )
    (net (code "85") (name "unconnected-(U1-(SS_{slash}_PCINT0)_PB0-Pad14)") (class "Default")
      (node (ref "U1") (pin "14") (pinfunction "(SS_/_PCINT0)_PB0_14") (pintype "passive+no_connect"))
    )
    (net (code "86") (name "unconnected-(U1-(~{RTS}_{slash}_AIN5_{slash}_INT6)_PD6-Pad12)") (class "Default")
      (node (ref "U1") (pin "12") (pinfunction "(~{RTS}_/_AIN5_/_INT6)_PD6_12") (pintype "passive+no_connect"))
    )
    (net (code "87") (name "unconnected-(U1-PC4_(PCINT10)-Pad26)") (class "Default")
      (node (ref "U1") (pin "26") (pinfunction "PC4_(PCINT10)_26") (pintype "passive+no_connect"))
    )
    (net (code "88") (name "unconnected-(U1-PC5_(_PCINT9{slash}_OC.1B)-Pad25)") (class "Default")
      (node (ref "U1") (pin "25") (pinfunction "PC5_(_PCINT9/_OC.1B)_25") (pintype "passive+no_connect"))
    )
    (net (code "89") (name "unconnected-(U1-PC6_(OC.1A_{slash}_PCINT8)-Pad23)") (class "Default")
      (node (ref "U1") (pin "23") (pinfunction "PC6_(OC.1A_/_PCINT8)_23") (pintype "passive+no_connect"))
    )
    (net (code "90") (name "unconnected-(U1-PC7_(INT4_{slash}_ICP1_{slash}_CLKO)-Pad22)") (class "Default")
      (node (ref "U1") (pin "22") (pinfunction "PC7_(INT4_/_ICP1_/_CLKO)_22") (pintype "passive+no_connect"))
    )
    (net (code "91") (name "unconnected-(U8-IO4-Pad26)") (class "Default")
      (node (ref "U8") (pin "26") (pinfunction "IO4_26") (pintype "bidirectional+no_connect"))
    )
    (net (code "92") (name "unconnected-(U8-IO5-Pad29)") (class "Default")
      (node (ref "U8") (pin "29") (pinfunction "IO5_29") (pintype "bidirectional+no_connect"))
    )
    (net (code "93") (name "unconnected-(U8-IO12-Pad14)") (class "Default")
      (node (ref "U8") (pin "14") (pinfunction "IO12_14") (pintype "bidirectional+no_connect"))
    )
    (net (code "94") (name "unconnected-(U8-IO13-Pad16)") (class "Default")
      (node (ref "U8") (pin "16") (pinfunction "IO13_16") (pintype "bidirectional"))
    )
    (net (code "95") (name "unconnected-(U8-IO14-Pad13)") (class "Default")
      (node (ref "U8") (pin "13") (pinfunction "IO14_13") (pintype "bidirectional+no_connect"))
    )
    (net (code "96") (name "unconnected-(U8-IO15-Pad23)") (class "Default")
      (node (ref "U8") (pin "23") (pinfunction "IO15_23") (pintype "bidirectional+no_connect"))
    )
    (net (code "97") (name "unconnected-(U8-IO16-Pad27)") (class "Default")
      (node (ref "U8") (pin "27") (pinfunction "IO16_27") (pintype "bidirectional+no_connect"))
    )
    (net (code "98") (name "unconnected-(U8-IO17-Pad28)") (class "Default")
      (node (ref "U8") (pin "28") (pinfunction "IO17_28") (pintype "bidirectional+no_connect"))
    )
    (net (code "99") (name "unconnected-(U8-IO18-Pad30)") (class "Default")
      (node (ref "U8") (pin "30") (pinfunction "IO18_30") (pintype "bidirectional+no_connect"))
    )
    (net (code "100") (name "unconnected-(U8-IO19-Pad31)") (class "Default")
      (node (ref "U8") (pin "31") (pinfunction "IO19_31") (pintype "bidirectional+no_connect"))
    )
    (net (code "101") (name "unconnected-(U8-IO21-Pad33)") (class "Default")
      (node (ref "U8") (pin "33") (pinfunction "IO21_33") (pintype "bidirectional+no_connect"))
    )
    (net (code "102") (name "unconnected-(U8-IO22-Pad36)") (class "Default")
      (node (ref "U8") (pin "36") (pinfunction "IO22_36") (pintype "bidirectional+no_connect"))
    )
    (net (code "103") (name "unconnected-(U8-IO23-Pad37)") (class "Default")
      (node (ref "U8") (pin "37") (pinfunction "IO23_37") (pintype "bidirectional+no_connect"))
    )
    (net (code "104") (name "unconnected-(U8-IO25-Pad10)") (class "Default")
      (node (ref "U8") (pin "10") (pinfunction "IO25_10") (pintype "bidirectional+no_connect"))
    )
    (net (code "105") (name "unconnected-(U8-IO26-Pad11)") (class "Default")
      (node (ref "U8") (pin "11") (pinfunction "IO26_11") (pintype "bidirectional+no_connect"))
    )
    (net (code "106") (name "unconnected-(U8-IO27-Pad12)") (class "Default")
      (node (ref "U8") (pin "12") (pinfunction "IO27_12") (pintype "bidirectional+no_connect"))
    )
    (net (code "107") (name "unconnected-(U8-IO32-Pad8)") (class "Default")
      (node (ref "U8") (pin "8") (pinfunction "IO32_8") (pintype "bidirectional+no_connect"))
    )
    (net (code "108") (name "unconnected-(U8-IO33-Pad9)") (class "Default")
      (node (ref "U8") (pin "9") (pinfunction "IO33_9") (pintype "bidirectional+no_connect"))
    )
    (net (code "109") (name "unconnected-(U8-IO34-Pad6)") (class "Default")
      (node (ref "U8") (pin "6") (pinfunction "IO34_6") (pintype "input+no_connect"))
    )
    (net (code "110") (name "unconnected-(U8-IO35-Pad7)") (class "Default")
      (node (ref "U8") (pin "7") (pinfunction "IO35_7") (pintype "input+no_connect"))
    )
    (net (code "111") (name "unconnected-(U8-NC-Pad17)") (class "Default")
      (node (ref "U8") (pin "17") (pinfunction "NC_17") (pintype "passive+no_connect"))
    )
    (net (code "112") (name "unconnected-(U8-NC-Pad18)") (class "Default")
      (node (ref "U8") (pin "18") (pinfunction "NC_18") (pintype "passive+no_connect"))
    )
    (net (code "113") (name "unconnected-(U8-NC-Pad19)") (class "Default")
      (node (ref "U8") (pin "19") (pinfunction "NC_19") (pintype "passive+no_connect"))
    )
    (net (code "114") (name "unconnected-(U8-NC-Pad20)") (class "Default")
      (node (ref "U8") (pin "20") (pinfunction "NC_20") (pintype "passive+no_connect"))
    )
    (net (code "115") (name "unconnected-(U8-NC-Pad21)") (class "Default")
      (node (ref "U8") (pin "21") (pinfunction "NC_21") (pintype "passive+no_connect"))
    )
    (net (code "116") (name "unconnected-(U8-NC-Pad22)") (class "Default")
      (node (ref "U8") (pin "22") (pinfunction "NC_22") (pintype "passive+no_connect"))
    )
    (net (code "117") (name "unconnected-(U8-NC-Pad32)") (class "Default")
      (node (ref "U8") (pin "32") (pinfunction "NC_32") (pintype "passive+no_connect"))
    )
    (net (code "118") (name "unconnected-(U8-SENSOR_VN-Pad5)") (class "Default")
      (node (ref "U8") (pin "5") (pinfunction "SENSOR_VN_5") (pintype "input+no_connect"))
    )
    (net (code "119") (name "unconnected-(U8-SENSOR_VP-Pad4)") (class "Default")
      (node (ref "U8") (pin "4") (pinfunction "SENSOR_VP_4") (pintype "input+no_connect"))
    )
    (net (code "120") (name "unconnected-(U9-NC-Pad4)") (class "Default")
      (node (ref "U9") (pin "4") (pinfunction "NC_4") (pintype "passive+no_connect"))
    )
  )
)
